# HMC2003_module.net
KiCad netlist of a schematic drawn in Altium Designer
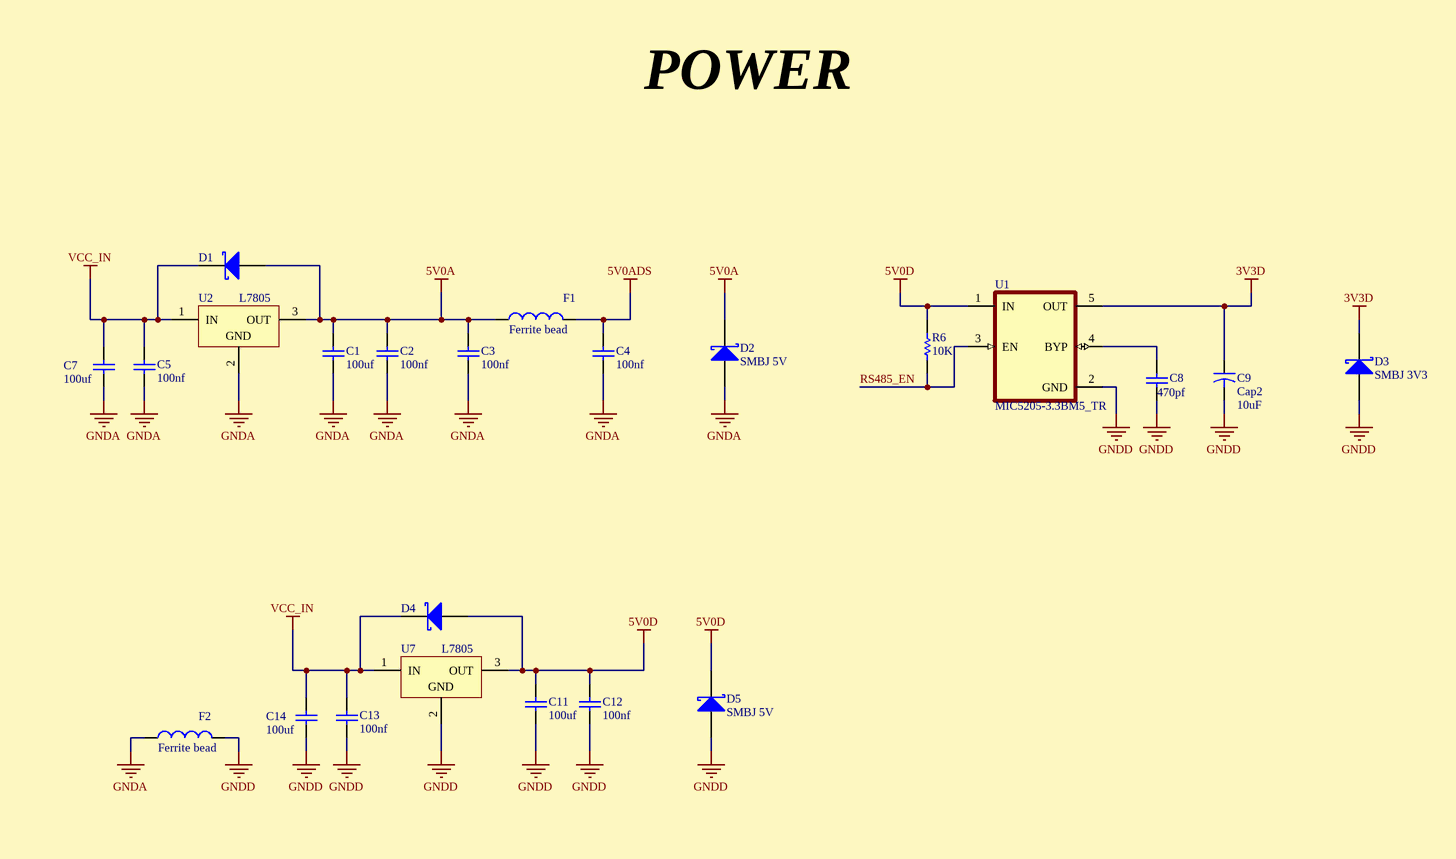
[diagram p0: HMC2003_module.SchDoc, top left]
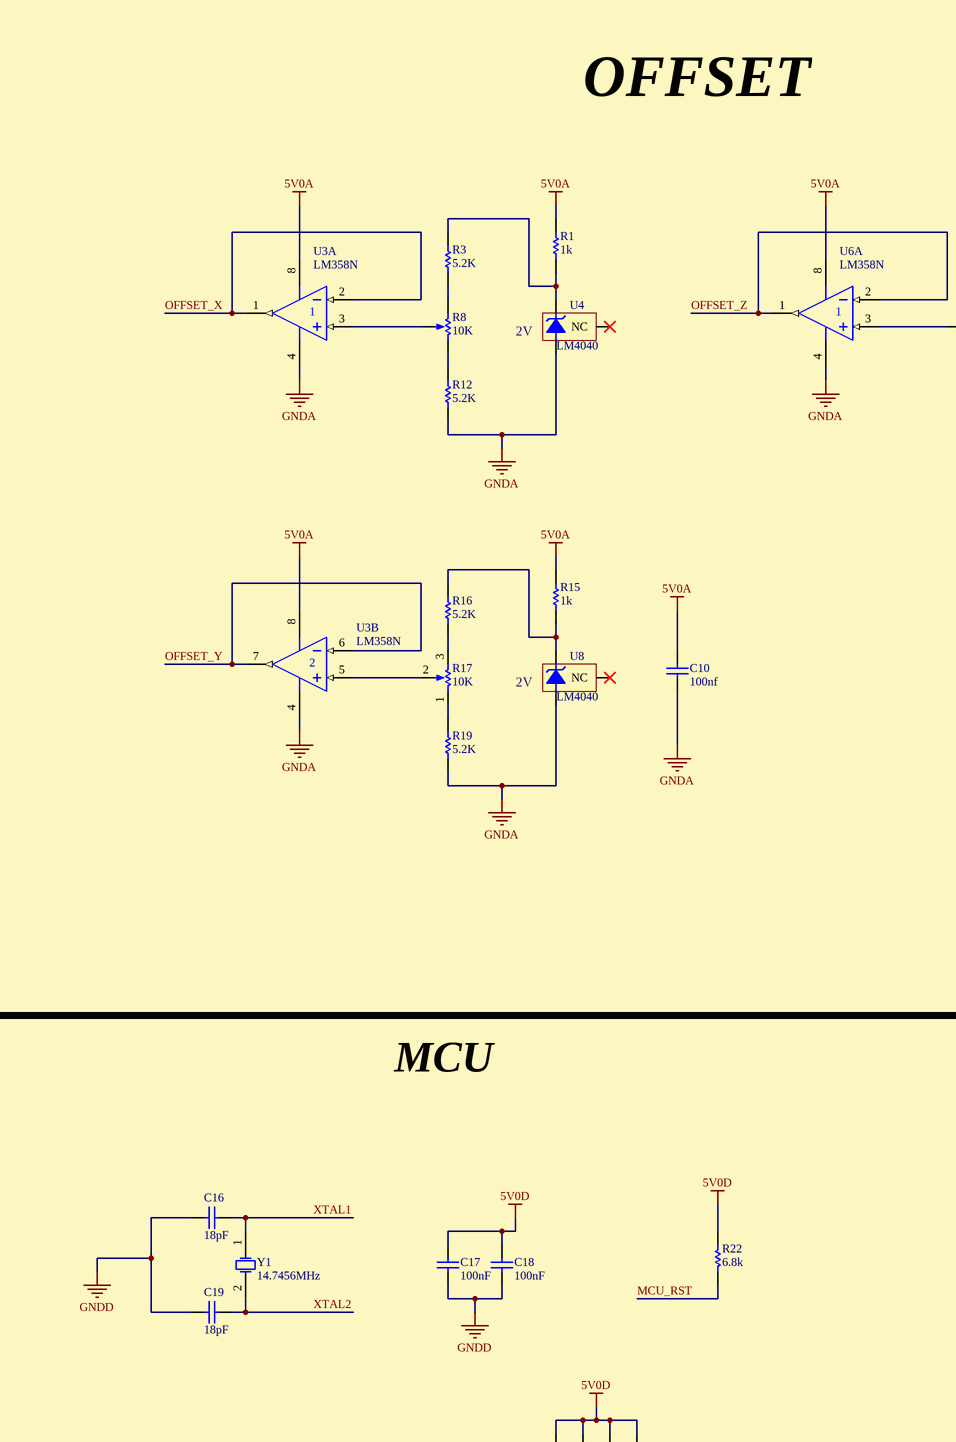
[diagram p1: HMC2003_module.SchDoc, top middle]
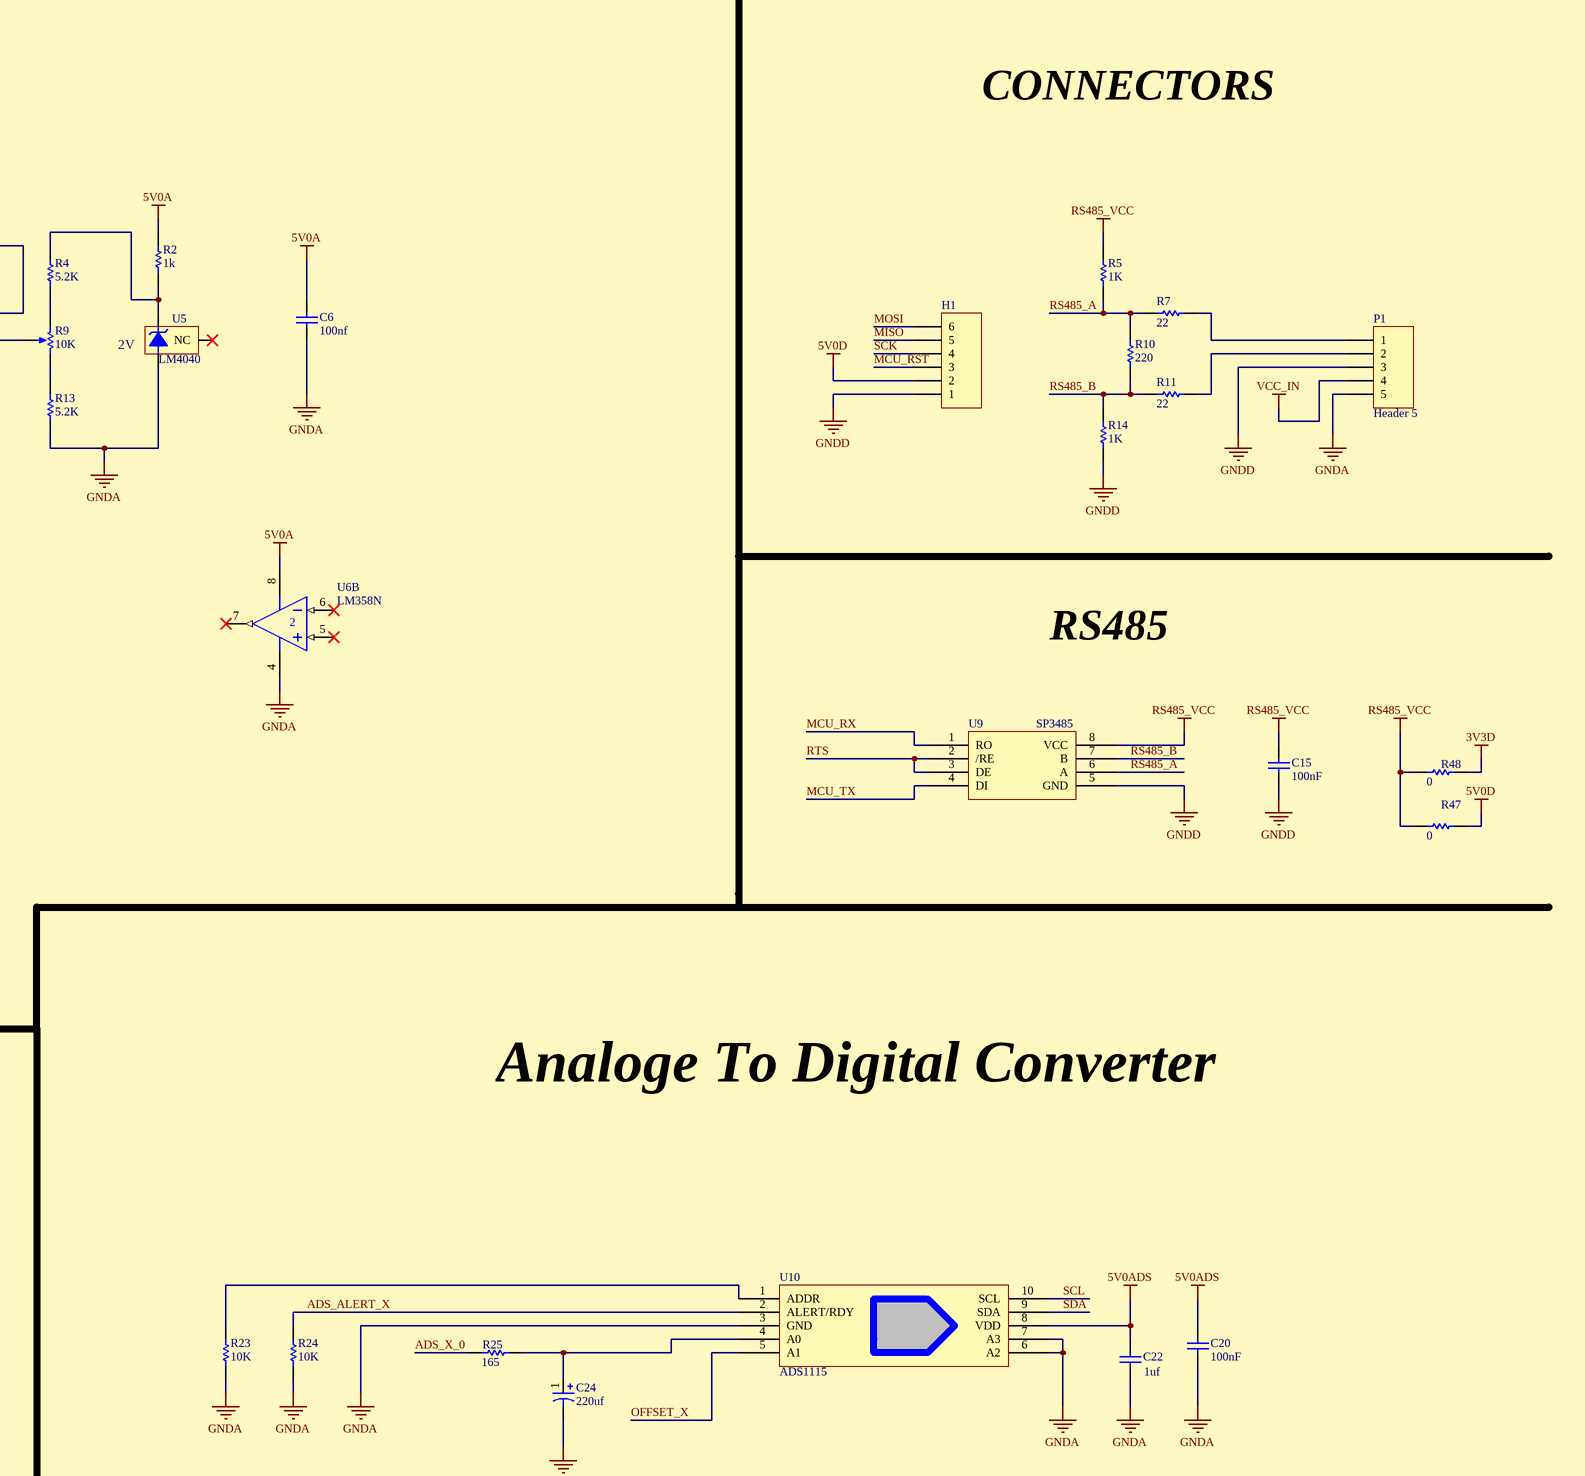
[diagram p2: HMC2003_module.SchDoc, top right]
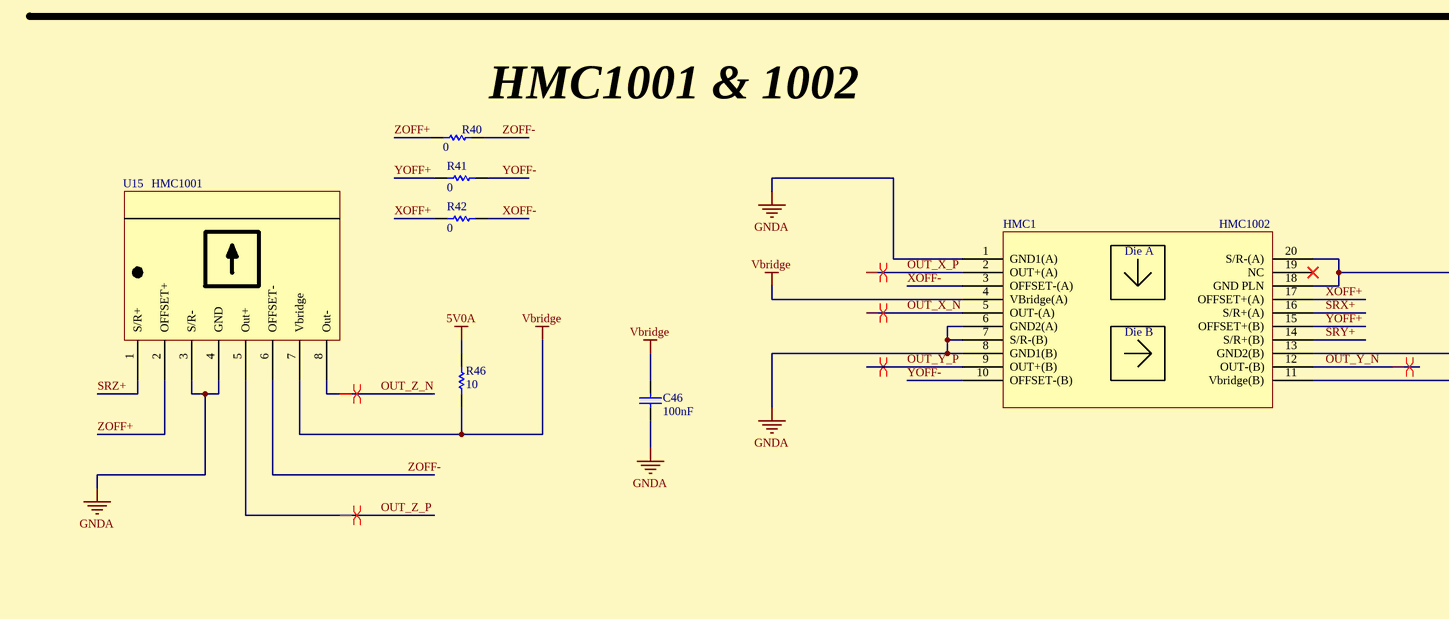
[diagram p3: HMC2003_module.SchDoc, bottom left]
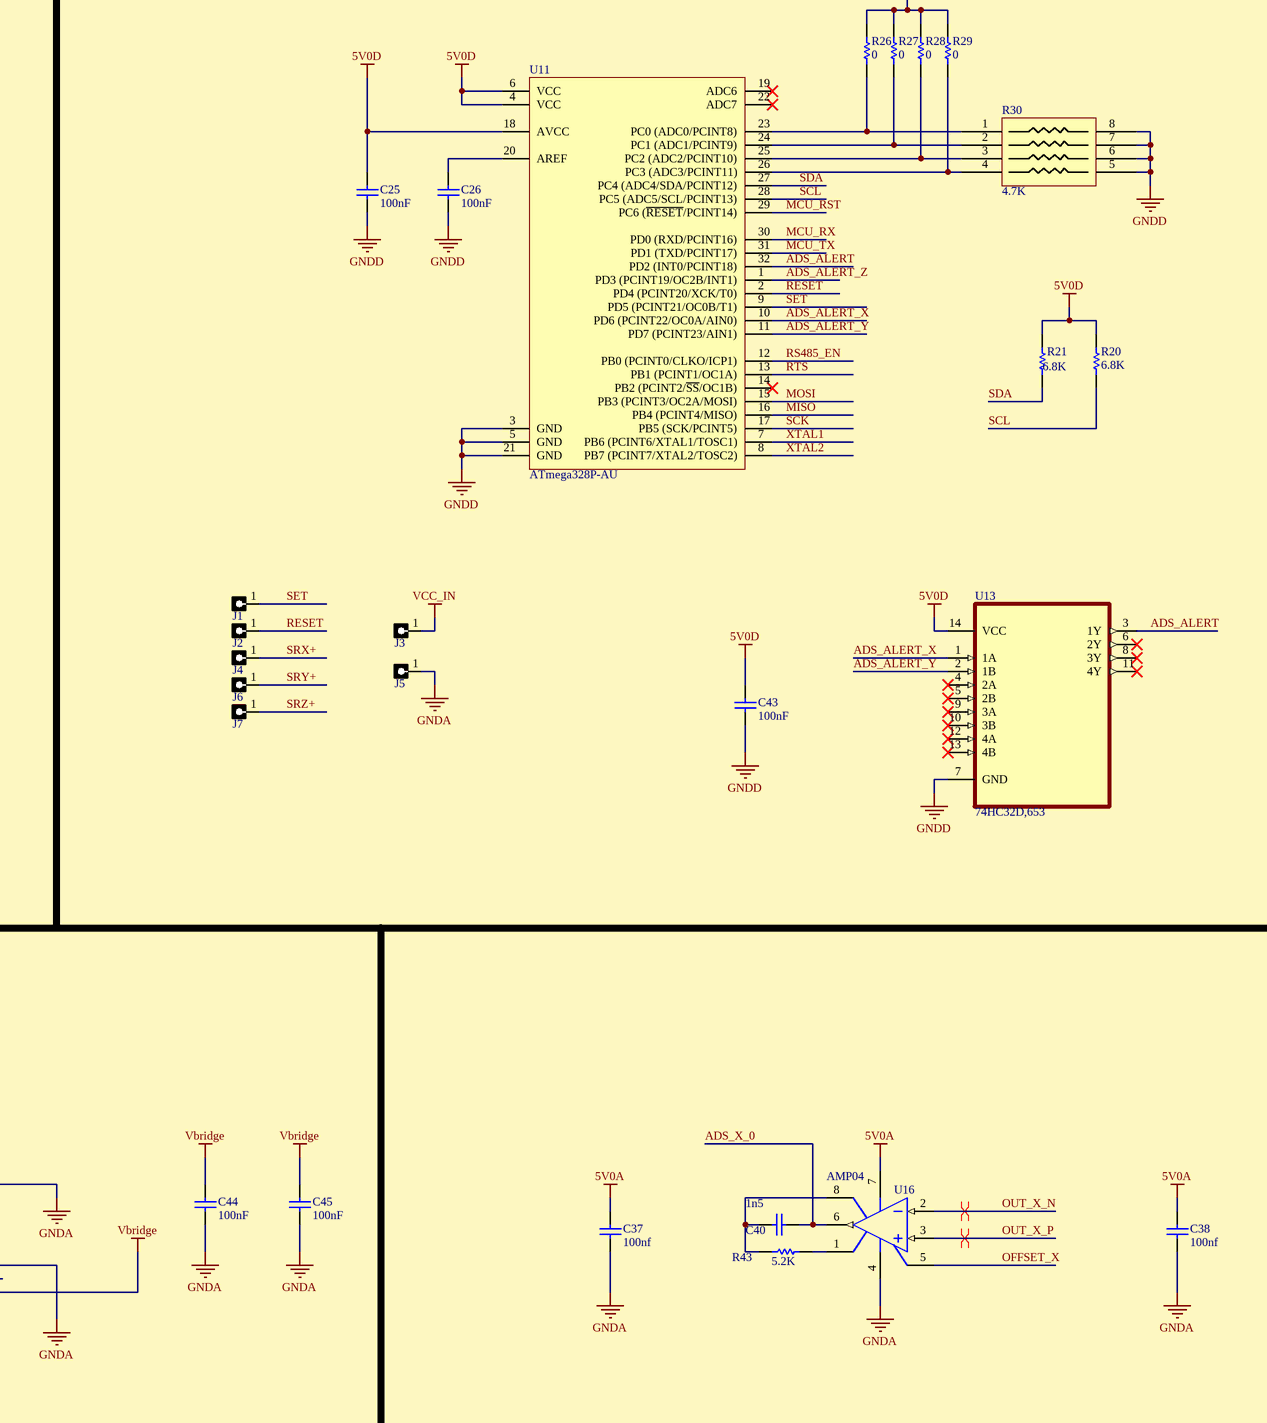
[diagram p4: HMC2003_module.SchDoc, bottom middle]
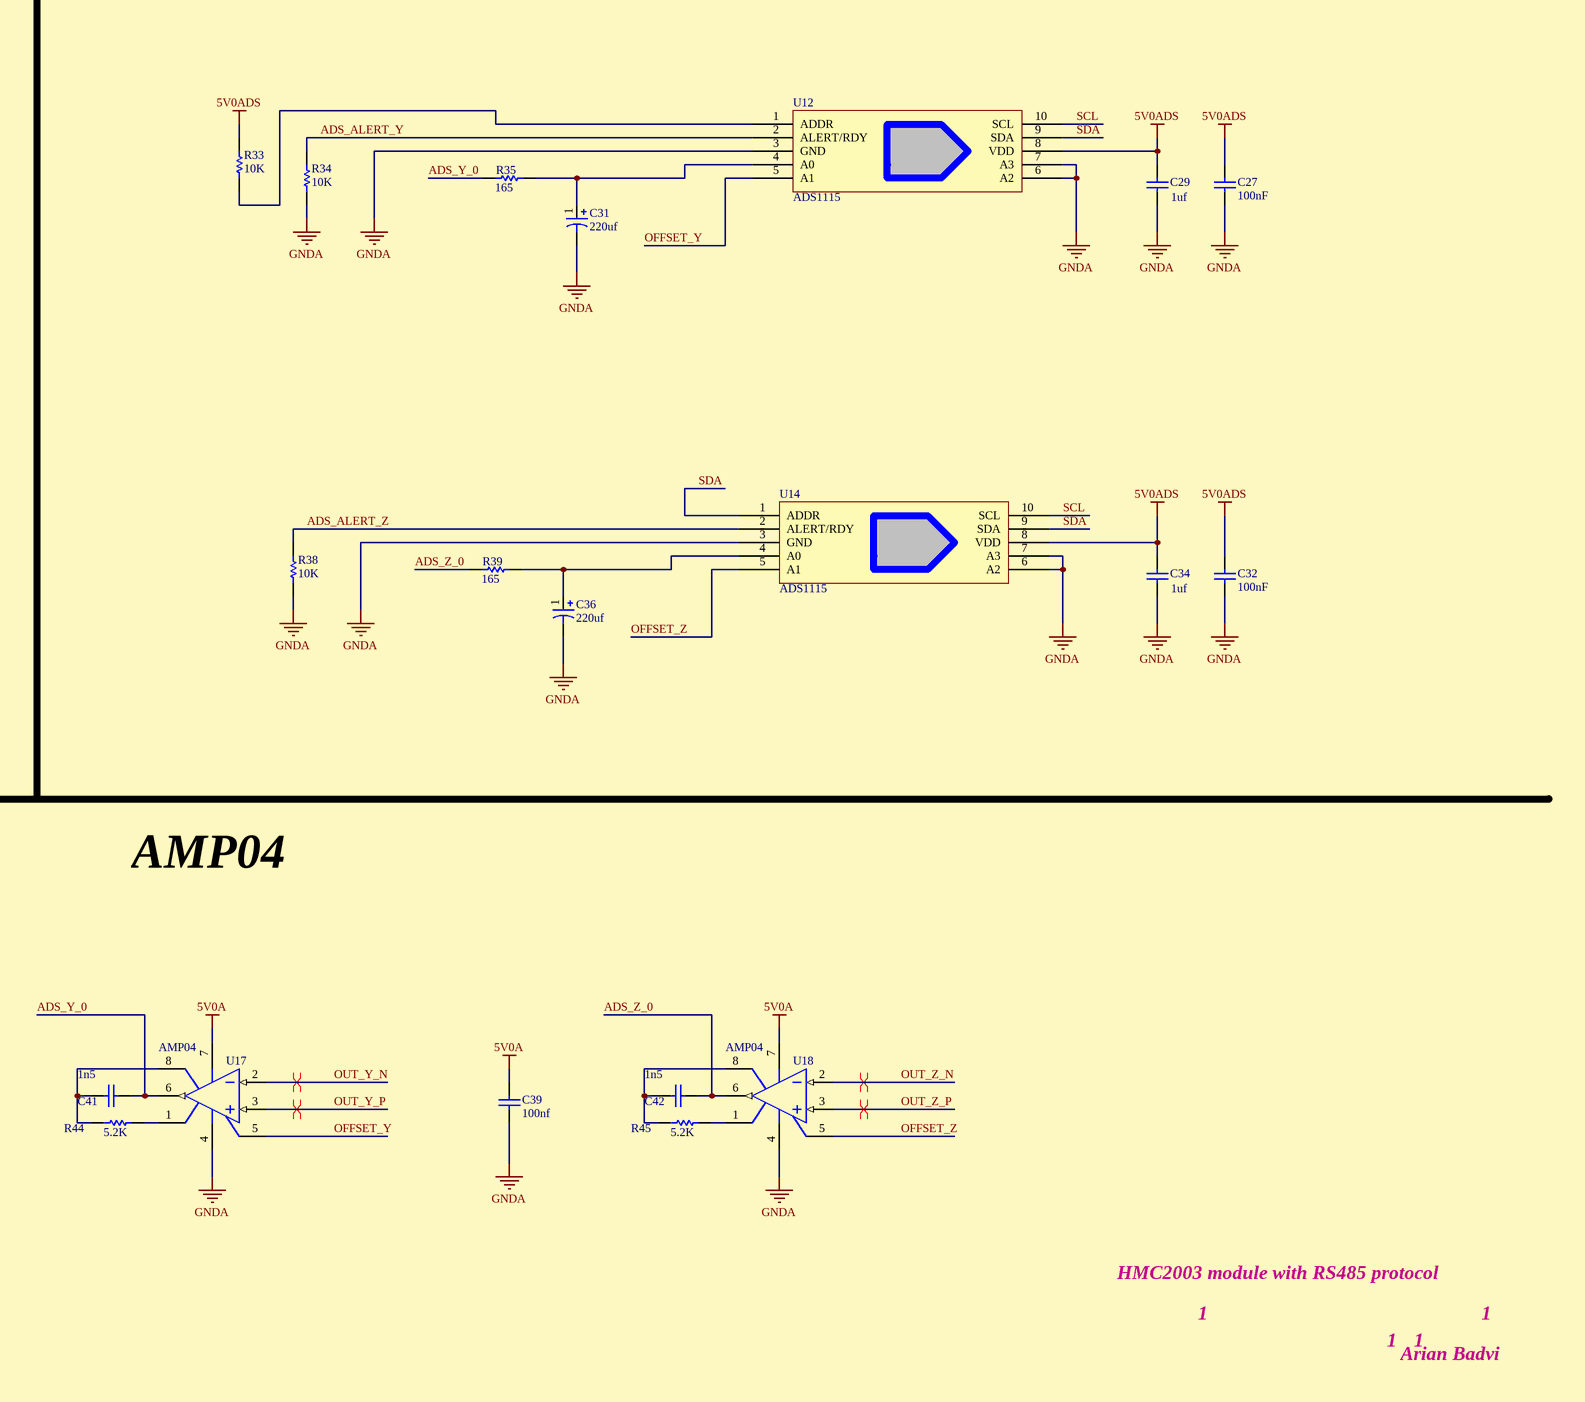
[diagram p5: HMC2003_module.SchDoc, bottom right]

(export (version "E")
  (design (tool "Eeschema 10.0.6"))
  (components
    (comp (ref "C1")
      (value "100uf")
      (footprint "C1206")
      (description "Capacitor, 1206")
      (fields (field (name "PUBLISHER") "Altium Limited"))
      (libsource (lib "Miscellaneous Devices") (part "Cap"))
    )
    (comp (ref "C2")
      (value "100nf")
      (footprint "C0805")
      (description "Capacitor, 1206")
      (fields (field (name "PUBLISHER") "Altium Limited"))
      (libsource (lib "Miscellaneous Devices") (part "Cap"))
    )
    (comp (ref "C3")
      (value "100nf")
      (footprint "C0805")
      (description "Capacitor, 1206")
      (fields (field (name "PUBLISHER") "Altium Limited"))
      (libsource (lib "Miscellaneous Devices") (part "Cap"))
    )
    (comp (ref "C4")
      (value "100nf")
      (footprint "C0805")
      (description "Capacitor, 1206")
      (fields (field (name "PUBLISHER") "Altium Limited"))
      (libsource (lib "Miscellaneous Devices") (part "Cap"))
    )
    (comp (ref "C5")
      (value "100nf")
      (footprint "C0805")
      (description "Capacitor, 1206")
      (fields (field (name "PUBLISHER") "Altium Limited"))
      (libsource (lib "Miscellaneous Devices") (part "Cap"))
    )
    (comp (ref "C6")
      (value "100nf")
      (footprint "C0805")
      (description "Capacitor")
      (fields (field (name "PUBLISHER") "Altium Limited"))
      (libsource (lib "Miscellaneous Devices") (part "Cap"))
    )
    (comp (ref "C7")
      (value "100uf")
      (footprint "C1206")
      (description "Capacitor, 1206")
      (fields (field (name "PUBLISHER") "Altium Limited"))
      (libsource (lib "Miscellaneous Devices") (part "Cap"))
    )
    (comp (ref "C8")
      (value "470pf")
      (footprint "C0805")
      (description "Capacitor, 1206")
      (fields (field (name "PUBLISHER") "Altium Limited"))
      (libsource (lib "Library") (part "Cap"))
    )
    (comp (ref "C9")
      (value "Cap2")
      (footprint "CAP_SMD_A")
      (description "Capacitor, 10uf")
      (fields (field (name "ALTIUM_VALUE") "10uF") (field (name "PUBLISHER") "Altium Limited"))
      (libsource (lib "Miscellaneous Devices") (part "Cap2"))
    )
    (comp (ref "C10")
      (value "100nf")
      (footprint "C0805")
      (description "Capacitor")
      (fields (field (name "PUBLISHER") "Altium Limited"))
      (libsource (lib "Miscellaneous Devices") (part "Cap"))
    )
    (comp (ref "C11")
      (value "100uf")
      (footprint "C1206")
      (description "Capacitor, 1206")
      (fields (field (name "PUBLISHER") "Altium Limited"))
      (libsource (lib "Miscellaneous Devices") (part "Cap"))
    )
    (comp (ref "C12")
      (value "100nf")
      (footprint "C0805")
      (description "Capacitor, 1206")
      (fields (field (name "PUBLISHER") "Altium Limited"))
      (libsource (lib "Miscellaneous Devices") (part "Cap"))
    )
    (comp (ref "C13")
      (value "100nf")
      (footprint "C0805")
      (description "Capacitor, 1206")
      (fields (field (name "PUBLISHER") "Altium Limited"))
      (libsource (lib "Miscellaneous Devices") (part "Cap"))
    )
    (comp (ref "C14")
      (value "100uf")
      (footprint "C1206")
      (description "Capacitor, 1206")
      (fields (field (name "PUBLISHER") "Altium Limited"))
      (libsource (lib "Miscellaneous Devices") (part "Cap"))
    )
    (comp (ref "C15")
      (value "100nF")
      (footprint "C0805")
      (description "Capacitor")
      (fields (field (name "PUBLISHER") "Altium Limited"))
      (libsource (lib "Miscellaneous Devices") (part "Cap"))
    )
    (comp (ref "C16")
      (value "18pF")
      (footprint "C0805")
      (description "Capacitor")
      (fields (field (name "PUBLISHER") "Altium Limited"))
      (libsource (lib "Miscellaneous Devices") (part "Cap"))
    )
    (comp (ref "C17")
      (value "100nF")
      (footprint "C0805")
      (description "Capacitor")
      (fields (field (name "PUBLISHER") "Altium Limited"))
      (libsource (lib "Miscellaneous Devices") (part "Cap"))
    )
    (comp (ref "C18")
      (value "100nF")
      (footprint "C0805")
      (description "Capacitor")
      (fields (field (name "PUBLISHER") "Altium Limited"))
      (libsource (lib "Miscellaneous Devices") (part "Cap"))
    )
    (comp (ref "C19")
      (value "18pF")
      (footprint "C0805")
      (description "Capacitor")
      (fields (field (name "PUBLISHER") "Altium Limited"))
      (libsource (lib "Miscellaneous Devices") (part "Cap"))
    )
    (comp (ref "C20")
      (value "100nF")
      (footprint "C0805")
      (description "Capacitor")
      (fields (field (name "PUBLISHER") "Altium Limited"))
      (libsource (lib "Miscellaneous Devices") (part "Cap"))
    )
    (comp (ref "C22")
      (value "1uf")
      (footprint "C0805")
      (description "Capacitor, 1206")
      (fields (field (name "PUBLISHER") "Altium Limited"))
      (libsource (lib "Library") (part "Cap"))
    )
    (comp (ref "C24")
      (value "220uf")
      (footprint "cap_smd_d")
      (description "TAN CAP D SIZE")
      (fields (field (name "PUBLISHER") "Altium Limited"))
      (libsource (lib "Miscellaneous Devices") (part "Cap Pol1"))
    )
    (comp (ref "C25")
      (value "100nF")
      (footprint "C0805")
      (description "Capacitor")
      (fields (field (name "PUBLISHER") "Altium Limited"))
      (libsource (lib "Miscellaneous Devices") (part "Cap"))
    )
    (comp (ref "C26")
      (value "100nF")
      (footprint "C0805")
      (description "Capacitor")
      (fields (field (name "PUBLISHER") "Altium Limited"))
      (libsource (lib "Miscellaneous Devices") (part "Cap"))
    )
    (comp (ref "C27")
      (value "100nF")
      (footprint "C0805")
      (description "Capacitor")
      (fields (field (name "PUBLISHER") "Altium Limited"))
      (libsource (lib "Miscellaneous Devices") (part "Cap"))
    )
    (comp (ref "C29")
      (value "1uf")
      (footprint "C0805")
      (description "Capacitor, 1206")
      (fields (field (name "PUBLISHER") "Altium Limited"))
      (libsource (lib "Library") (part "Cap"))
    )
    (comp (ref "C31")
      (value "220uf")
      (footprint "cap_smd_d")
      (description "TAN CAP D SIZE")
      (fields (field (name "PUBLISHER") "Altium Limited"))
      (libsource (lib "Miscellaneous Devices") (part "Cap Pol1"))
    )
    (comp (ref "C32")
      (value "100nF")
      (footprint "C0805")
      (description "Capacitor")
      (fields (field (name "PUBLISHER") "Altium Limited"))
      (libsource (lib "Miscellaneous Devices") (part "Cap"))
    )
    (comp (ref "C34")
      (value "1uf")
      (footprint "C0805")
      (description "Capacitor, 1206")
      (fields (field (name "PUBLISHER") "Altium Limited"))
      (libsource (lib "Library") (part "Cap"))
    )
    (comp (ref "C36")
      (value "220uf")
      (footprint "cap_smd_d")
      (description "TAN CAP D SIZE")
      (fields (field (name "PUBLISHER") "Altium Limited"))
      (libsource (lib "Miscellaneous Devices") (part "Cap Pol1"))
    )
    (comp (ref "C37")
      (value "100nf")
      (footprint "C0805")
      (description "Capacitor")
      (fields (field (name "PUBLISHER") "Altium Limited"))
      (libsource (lib "Miscellaneous Devices") (part "Cap"))
    )
    (comp (ref "C38")
      (value "100nf")
      (footprint "C0805")
      (description "Capacitor")
      (fields (field (name "PUBLISHER") "Altium Limited"))
      (libsource (lib "Miscellaneous Devices") (part "Cap"))
    )
    (comp (ref "C39")
      (value "100nf")
      (footprint "C0805")
      (description "Capacitor")
      (fields (field (name "PUBLISHER") "Altium Limited"))
      (libsource (lib "Miscellaneous Devices") (part "Cap"))
    )
    (comp (ref "C40")
      (value "1n5")
      (footprint "C0805")
      (description "Capacitor")
      (fields (field (name "PUBLISHER") "Altium Limited"))
      (libsource (lib "Library") (part "Cap"))
    )
    (comp (ref "C41")
      (value "1n5")
      (footprint "C0805")
      (description "Capacitor")
      (fields (field (name "PUBLISHER") "Altium Limited"))
      (libsource (lib "Library") (part "Cap"))
    )
    (comp (ref "C42")
      (value "1n5")
      (footprint "C0805")
      (description "Capacitor")
      (fields (field (name "PUBLISHER") "Altium Limited"))
      (libsource (lib "Library") (part "Cap"))
    )
    (comp (ref "C43")
      (value "100nF")
      (footprint "C0805")
      (description "Capacitor")
      (fields (field (name "PUBLISHER") "Altium Limited"))
      (libsource (lib "Miscellaneous Devices") (part "Cap"))
    )
    (comp (ref "C44")
      (value "100nF")
      (footprint "C0805")
      (description "Capacitor")
      (fields (field (name "PUBLISHER") "Altium Limited"))
      (libsource (lib "Miscellaneous Devices") (part "Cap"))
    )
    (comp (ref "C45")
      (value "100nF")
      (footprint "C0805")
      (description "Capacitor")
      (fields (field (name "PUBLISHER") "Altium Limited"))
      (libsource (lib "Miscellaneous Devices") (part "Cap"))
    )
    (comp (ref "C46")
      (value "100nF")
      (footprint "C0805")
      (description "Capacitor")
      (fields (field (name "PUBLISHER") "Altium Limited"))
      (libsource (lib "Miscellaneous Devices") (part "Cap"))
    )
    (comp (ref "D1")
      (value "D Schottky")
      (footprint "ZENER")
      (description "Schottky Diode, 1N4148")
      (fields (field (name "PUBLISHER") "Altium Limited"))
      (libsource (lib "Miscellaneous Devices") (part "D Schottky"))
    )
    (comp (ref "D2")
      (value "SMBJ 5V")
      (footprint "TVS")
      (description "Schottky Rectifier")
      (fields (field (name "PUBLISHER") "Altium Limited"))
      (libsource (lib "") (part "Diode 18TQ045_1"))
    )
    (comp (ref "D3")
      (value "SMBJ 3V3")
      (footprint "TVS")
      (description "TVS")
      (fields (field (name "PUBLISHER") "Altium Limited"))
      (libsource (lib "Miscellaneous Devices") (part "Diode 18TQ045"))
    )
    (comp (ref "D4")
      (value "D Schottky")
      (footprint "ZENER")
      (description "Schottky Diode, 1N4148")
      (fields (field (name "PUBLISHER") "Altium Limited"))
      (libsource (lib "Miscellaneous Devices") (part "D Schottky"))
    )
    (comp (ref "D5")
      (value "SMBJ 5V")
      (footprint "TVS")
      (description "Schottky Rectifier")
      (fields (field (name "PUBLISHER") "Altium Limited"))
      (libsource (lib "") (part "Diode 18TQ045_1"))
    )
    (comp (ref "F1")
      (value "Ferrite bead")
      (footprint "0805")
      (description "Ferrite bead, 1206")
      (fields (field (name "PUBLISHER") "Altium Limited"))
      (libsource (lib "Miscellaneous Devices") (part "Inductor"))
    )
    (comp (ref "F2")
      (value "Ferrite bead")
      (footprint "0805")
      (description "Ferrite bead, 1206")
      (fields (field (name "PUBLISHER") "Altium Limited"))
      (libsource (lib "Miscellaneous Devices") (part "Inductor"))
    )
    (comp (ref "H1")
      (value "White SMD Connector 6pin")
      (footprint "PB_6_SMD")
      (fields (field (name "PUBLISHER") "Altium Limited"))
      (libsource (lib "Miscellaneous Connectors") (part "Header 6"))
    )
    (comp (ref "HMC1") (value "HMC1002") (footprint "SO_20_W") (libsource (lib "HMC1002") (part "HMC1002")))
    (comp (ref "J1")
      (value "HDRF1")
      (footprint "HDR_F_1")
      (description "CONN, HEADER, Female, pitch: 2.54mm, 1POS")
      (libsource (lib "A7DDS") (part "HDR_F_1"))
    )
    (comp (ref "J2")
      (value "HDRF1")
      (footprint "HDR_F_1")
      (description "CONN, HEADER, Female, pitch: 2.54mm, 1POS")
      (libsource (lib "A7DDS") (part "HDR_F_1"))
    )
    (comp (ref "J3")
      (value "HDRF1")
      (footprint "HDR_F_1")
      (description "CONN, HEADER, Female, pitch: 2.54mm, 1POS")
      (libsource (lib "A7DDS") (part "HDR_F_1"))
    )
    (comp (ref "J4")
      (value "HDRF1")
      (footprint "HDR_F_1")
      (description "CONN, HEADER, Female, pitch: 2.54mm, 1POS")
      (libsource (lib "A7DDS") (part "HDR_F_1"))
    )
    (comp (ref "J5")
      (value "HDRF1")
      (footprint "HDR_F_1")
      (description "CONN, HEADER, Female, pitch: 2.54mm, 1POS")
      (libsource (lib "A7DDS") (part "HDR_F_1"))
    )
    (comp (ref "J6")
      (value "HDRF1")
      (footprint "HDR_F_1")
      (description "CONN, HEADER, Female, pitch: 2.54mm, 1POS")
      (libsource (lib "A7DDS") (part "HDR_F_1"))
    )
    (comp (ref "J7")
      (value "HDRF1")
      (footprint "HDR_F_1")
      (description "CONN, HEADER, Female, pitch: 2.54mm, 1POS")
      (libsource (lib "A7DDS") (part "HDR_F_1"))
    )
    (comp (ref "P1")
      (value "Header 5")
      (footprint "HDR_M_1x5")
      (description "Header, 5-Pin")
      (fields (field (name "PUBLISHER") "Altium Limited"))
      (libsource (lib "Miscellaneous Connectors") (part "Header 5"))
    )
    (comp (ref "R1")
      (value "1k")
      (footprint "0805")
      (description "Resistor")
      (fields (field (name "PUBLISHER") "Seyed Razi Vesali") (field (name "EMAIL") "razi.vesali@gmail.com"))
      (libsource (lib "resistor1") (part "Resistor"))
    )
    (comp (ref "R2")
      (value "1k")
      (footprint "0805")
      (description "Resistor")
      (fields (field (name "PUBLISHER") "Seyed Razi Vesali") (field (name "EMAIL") "razi.vesali@gmail.com"))
      (libsource (lib "resistor1") (part "Resistor"))
    )
    (comp (ref "R3")
      (value "5.2K")
      (footprint "0805")
      (description "General Resistor")
      (fields (field (name "PUBLISHER") "Altium Limited"))
      (libsource (lib "Library") (part "Resistor"))
    )
    (comp (ref "R4")
      (value "5.2K")
      (footprint "0805")
      (description "General Resistor")
      (fields (field (name "PUBLISHER") "Altium Limited"))
      (libsource (lib "Library") (part "Resistor"))
    )
    (comp (ref "R5")
      (value "1K")
      (footprint "0805")
      (description "Resistor")
      (fields (field (name "PUBLISHER") "Altium Limited"))
      (libsource (lib "Miscellaneous Devices") (part "Res1"))
    )
    (comp (ref "R6")
      (value "10K")
      (footprint "0805")
      (description "General Resistor")
      (fields (field (name "PUBLISHER") "Altium Limited"))
      (libsource (lib "Library") (part "Resistor"))
    )
    (comp (ref "R7")
      (value "22")
      (footprint "0805")
      (description "Resistor")
      (fields (field (name "PUBLISHER") "Altium Limited"))
      (libsource (lib "Miscellaneous Devices") (part "Res1"))
    )
    (comp (ref "R8")
      (value "10K")
      (footprint "POT_3296w")
      (description "Potentiometer")
      (fields (field (name "Comment") "RPot") (field (name "PUBLISHER") "Altium Limited"))
      (libsource (lib "") (part "RPot_1"))
    )
    (comp (ref "R9")
      (value "10K")
      (footprint "POT_3296w")
      (description "Potentiometer")
      (fields (field (name "Comment") "RPot") (field (name "PUBLISHER") "Altium Limited"))
      (libsource (lib "") (part "RPot_1"))
    )
    (comp (ref "R10")
      (value "220")
      (footprint "0805")
      (description "Resistor")
      (fields (field (name "PUBLISHER") "Altium Limited"))
      (libsource (lib "Miscellaneous Devices") (part "Res1"))
    )
    (comp (ref "R11")
      (value "22")
      (footprint "0805")
      (description "Resistor")
      (fields (field (name "PUBLISHER") "Altium Limited"))
      (libsource (lib "Miscellaneous Devices") (part "Res1"))
    )
    (comp (ref "R12")
      (value "5.2K")
      (footprint "0805")
      (description "General Resistor")
      (fields (field (name "PUBLISHER") "Altium Limited"))
      (libsource (lib "Library") (part "Resistor"))
    )
    (comp (ref "R13")
      (value "5.2K")
      (footprint "0805")
      (description "General Resistor")
      (fields (field (name "PUBLISHER") "Altium Limited"))
      (libsource (lib "Library") (part "Resistor"))
    )
    (comp (ref "R14")
      (value "1K")
      (footprint "0805")
      (description "Resistor")
      (fields (field (name "PUBLISHER") "Altium Limited"))
      (libsource (lib "Miscellaneous Devices") (part "Res1"))
    )
    (comp (ref "R15")
      (value "1k")
      (footprint "0805")
      (description "Resistor")
      (fields (field (name "PUBLISHER") "Seyed Razi Vesali") (field (name "EMAIL") "razi.vesali@gmail.com"))
      (libsource (lib "resistor1") (part "Resistor"))
    )
    (comp (ref "R16")
      (value "5.2K")
      (footprint "0805")
      (description "General Resistor")
      (fields (field (name "PUBLISHER") "Altium Limited"))
      (libsource (lib "Library") (part "Resistor"))
    )
    (comp (ref "R17")
      (value "10K")
      (footprint "POT_3296w")
      (description "Potentiometer")
      (fields (field (name "Comment") "RPot") (field (name "PUBLISHER") "Altium Limited"))
      (libsource (lib "Miscellaneous Devices") (part "RPot"))
    )
    (comp (ref "R19")
      (value "5.2K")
      (footprint "0805")
      (description "General Resistor")
      (fields (field (name "PUBLISHER") "Altium Limited"))
      (libsource (lib "Library") (part "Resistor"))
    )
    (comp (ref "R20")
      (value "6.8K")
      (footprint "0805")
      (description "General Resistor")
      (fields (field (name "PUBLISHER") "Altium Limited"))
      (libsource (lib "Library") (part "Resistor"))
    )
    (comp (ref "R21")
      (value "6.8K")
      (footprint "0805")
      (description "General Resistor")
      (fields (field (name "PUBLISHER") "Altium Limited"))
      (libsource (lib "Library") (part "Resistor"))
    )
    (comp (ref "R22")
      (value "6.8k")
      (footprint "0805")
      (description "Resistor, 6.8k")
      (fields (field (name "PUBLISHER") "Altium Limited"))
      (libsource (lib "Miscellaneous Devices") (part "Res1"))
    )
    (comp (ref "R23")
      (value "10K")
      (footprint "0805")
      (description "General Resistor")
      (fields (field (name "PUBLISHER") "Altium Limited"))
      (libsource (lib "Library") (part "Resistor"))
    )
    (comp (ref "R24")
      (value "10K")
      (footprint "0805")
      (description "General Resistor")
      (fields (field (name "PUBLISHER") "Altium Limited"))
      (libsource (lib "Library") (part "Resistor"))
    )
    (comp (ref "R25")
      (value "165")
      (footprint "0805")
      (description "General Resistor")
      (fields (field (name "PUBLISHER") "Altium Limited"))
      (libsource (lib "Library") (part "Resistor"))
    )
    (comp (ref "R26")
      (value "0")
      (footprint "0603")
      (description "Resistor, 6.8k")
      (fields (field (name "PUBLISHER") "Altium Limited"))
      (libsource (lib "Miscellaneous Devices") (part "Res1"))
    )
    (comp (ref "R27")
      (value "0")
      (footprint "0603")
      (description "Resistor, 6.8k")
      (fields (field (name "PUBLISHER") "Altium Limited"))
      (libsource (lib "Miscellaneous Devices") (part "Res1"))
    )
    (comp (ref "R28")
      (value "0")
      (footprint "0603")
      (description "Resistor, 6.8k")
      (fields (field (name "PUBLISHER") "Altium Limited"))
      (libsource (lib "Miscellaneous Devices") (part "Res1"))
    )
    (comp (ref "R29")
      (value "0")
      (footprint "0603")
      (description "Resistor, 6.8k")
      (fields (field (name "PUBLISHER") "Altium Limited"))
      (libsource (lib "Miscellaneous Devices") (part "Res1"))
    )
    (comp (ref "R30")
      (value "4.7K")
      (footprint "RP0603X4")
      (libsource (lib "RES_ARRAY_4") (part "RES_ARRAY_4"))
    )
    (comp (ref "R33")
      (value "10K")
      (footprint "0805")
      (description "General Resistor")
      (fields (field (name "PUBLISHER") "Altium Limited"))
      (libsource (lib "Library") (part "Resistor"))
    )
    (comp (ref "R34")
      (value "10K")
      (footprint "0805")
      (description "General Resistor")
      (fields (field (name "PUBLISHER") "Altium Limited"))
      (libsource (lib "Library") (part "Resistor"))
    )
    (comp (ref "R35")
      (value "165")
      (footprint "0805")
      (description "General Resistor")
      (fields (field (name "PUBLISHER") "Altium Limited"))
      (libsource (lib "Library") (part "Resistor"))
    )
    (comp (ref "R38")
      (value "10K")
      (footprint "0805")
      (description "General Resistor")
      (fields (field (name "PUBLISHER") "Altium Limited"))
      (libsource (lib "Library") (part "Resistor"))
    )
    (comp (ref "R39")
      (value "165")
      (footprint "0805")
      (description "General Resistor")
      (fields (field (name "PUBLISHER") "Altium Limited"))
      (libsource (lib "Library") (part "Resistor"))
    )
    (comp (ref "R40")
      (value "0")
      (footprint "0603")
      (description "Resistor")
      (fields (field (name "PUBLISHER") "Seyed Razi Vesali") (field (name "EMAIL") "razi.vesali@gmail.com"))
      (libsource (lib "resistor1") (part "Resistor"))
    )
    (comp (ref "R41")
      (value "0")
      (footprint "0603")
      (description "Resistor")
      (fields (field (name "PUBLISHER") "Seyed Razi Vesali") (field (name "EMAIL") "razi.vesali@gmail.com"))
      (libsource (lib "resistor1") (part "Resistor"))
    )
    (comp (ref "R42")
      (value "0")
      (footprint "0603")
      (description "Resistor")
      (fields (field (name "PUBLISHER") "Seyed Razi Vesali") (field (name "EMAIL") "razi.vesali@gmail.com"))
      (libsource (lib "resistor1") (part "Resistor"))
    )
    (comp (ref "R43")
      (value "5.2K")
      (footprint "0805")
      (description "General Resistor")
      (fields (field (name "PUBLISHER") "Altium Limited"))
      (libsource (lib "Library") (part "Resistor"))
    )
    (comp (ref "R44")
      (value "5.2K")
      (footprint "0805")
      (description "General Resistor")
      (fields (field (name "PUBLISHER") "Altium Limited"))
      (libsource (lib "Library") (part "Resistor"))
    )
    (comp (ref "R45")
      (value "5.2K")
      (footprint "0805")
      (description "General Resistor")
      (fields (field (name "PUBLISHER") "Altium Limited"))
      (libsource (lib "Library") (part "Resistor"))
    )
    (comp (ref "R46")
      (value "10")
      (footprint "0805")
      (description "Resistor")
      (fields (field (name "PUBLISHER") "Seyed Razi Vesali") (field (name "EMAIL") "razi.vesali@gmail.com"))
      (libsource (lib "resistor1") (part "Resistor"))
    )
    (comp (ref "R47")
      (value "0")
      (footprint "0603")
      (description "Resistor")
      (fields (field (name "PUBLISHER") "Seyed Razi Vesali") (field (name "EMAIL") "razi.vesali@gmail.com"))
      (libsource (lib "resistor1") (part "Resistor"))
    )
    (comp (ref "R48")
      (value "0")
      (footprint "0603")
      (description "Resistor")
      (fields (field (name "PUBLISHER") "Seyed Razi Vesali") (field (name "EMAIL") "razi.vesali@gmail.com"))
      (libsource (lib "resistor1") (part "Resistor"))
    )
    (comp (ref "U1")
      (value "MIC5205-3.3BM5_TR")
      (footprint "SOT23_5")
      (description "Linear Voltage Regulator IC 1 Output 150mA SOT-23-5")
      (fields (field (name "MP") "MIC5205-3.3BM5 TR") (field (name "MF") "Micrel"))
      (libsource (lib "Main_board") (part "MIC5205-3.3BM5_TR"))
    )
    (comp (ref "U2")
      (value "L7805")
      (footprint "DPAK")
      (description "Positive Voltage Regulator")
      (fields (field (name "PUBLISHER") "Altium Limited"))
      (libsource (lib "ST Power Mgt Voltage Regulator") (part "L7805CD2T"))
    )
    (comp (ref "U3")
      (value "LM358N")
      (footprint "sop8")
      (description "Dual Low-Power Operational Amplifier")
      (fields (field (name "PUBLISHER") "Altium Limited"))
      (libsource (lib "Motorola Amplifier Operational Amplifier") (part "LM358N"))
    )
    (comp (ref "U4")
      (value "LM4040")
      (footprint "sot-23")
      (description "Precision Micropower Shunt Voltage Reference, 3-pin SOT-23")
      (fields
        (field (name "PARTNUMBER") "LM4040DIM3-10.0")
        (field (name "MANUFACTURER") "National Semiconductor")
        (field (name "PUBLISHER") "Altium Limited")
      )
      (libsource (lib "final_sensor_sch_lib") (part "LM4040"))
    )
    (comp (ref "U5")
      (value "LM4040")
      (footprint "sot-23")
      (description "Precision Micropower Shunt Voltage Reference, 3-pin SOT-23")
      (fields
        (field (name "PARTNUMBER") "LM4040DIM3-10.0")
        (field (name "MANUFACTURER") "National Semiconductor")
        (field (name "PUBLISHER") "Altium Limited")
      )
      (libsource (lib "final_sensor_sch_lib") (part "LM4040"))
    )
    (comp (ref "U6")
      (value "LM358N")
      (footprint "sop8")
      (description "Dual Low-Power Operational Amplifier")
      (fields (field (name "PUBLISHER") "Altium Limited"))
      (libsource (lib "Motorola Amplifier Operational Amplifier") (part "LM358N"))
    )
    (comp (ref "U7")
      (value "L7805")
      (footprint "DPAK")
      (description "Positive Voltage Regulator")
      (fields (field (name "PUBLISHER") "Altium Limited"))
      (libsource (lib "ST Power Mgt Voltage Regulator") (part "L7805CD2T"))
    )
    (comp (ref "U8")
      (value "LM4040")
      (footprint "sot-23")
      (description "Precision Micropower Shunt Voltage Reference, 3-pin SOT-23")
      (fields
        (field (name "PARTNUMBER") "LM4040DIM3-10.0")
        (field (name "MANUFACTURER") "National Semiconductor")
        (field (name "PUBLISHER") "Altium Limited")
      )
      (libsource (lib "final_sensor_sch_lib") (part "LM4040"))
    )
    (comp (ref "U9") (value "SP3485") (footprint "SOP8") (libsource (lib "Schlib_RS485") (part "rs485")))
    (comp (ref "U10") (value "ADS1115") (footprint "TSSOP10_N") (libsource (lib "Library") (part "ADS1115")))
    (comp (ref "U11")
      (value "ATmega328P-AU")
      (footprint "32A_L")
      (fields (field (name "PUBLISHER") "Altium Limited"))
      (libsource (lib "Library") (part "ATmega328P-AU"))
    )
    (comp (ref "U12") (value "ADS1115") (footprint "TSSOP10_N") (libsource (lib "Library") (part "ADS1115")))
    (comp (ref "U13")
      (value "74HC32D,653")
      (footprint "SOG65_14")
      (description "OR Gate IC 4 Channel 14-SO")
      (fields (field (name "MF") "Nexperia USA"))
      (libsource (lib "74HC32D_653") (part "74HC32D,653"))
    )
    (comp (ref "U14") (value "ADS1115") (footprint "TSSOP10_N") (libsource (lib "Library") (part "ADS1115")))
    (comp (ref "U15") (value "HMC1001") (footprint "HMC1001_V") (libsource (lib "Library") (part "HMC1001")))
    (comp (ref "U16")
      (value "AMP04")
      (footprint "sop8")
      (fields (field (name "PUBLISHER") "Altium Limited"))
      (libsource (lib "Miscellaneous Devices") (part "Op Amp"))
    )
    (comp (ref "U17")
      (value "AMP04")
      (footprint "sop8")
      (fields (field (name "PUBLISHER") "Altium Limited"))
      (libsource (lib "Miscellaneous Devices") (part "Op Amp"))
    )
    (comp (ref "U18")
      (value "AMP04")
      (footprint "sop8")
      (fields (field (name "PUBLISHER") "Altium Limited"))
      (libsource (lib "Miscellaneous Devices") (part "Op Amp"))
    )
    (comp (ref "Y1")
      (value "14.7456MHz")
      (footprint "XTAL_SMD")
      (description "Crystal Oscillator, 14.7456KHz")
      (fields (field (name "PUBLISHER") "Altium Limited"))
      (libsource (lib "Miscellaneous Devices") (part "XTAL"))
    )
  )
  (nets
    (net (code "1") (name "/ADS_ALERT") (class "Default")
      (node (ref "U11") (pin "32") (pinfunction "PD2_(INT0/PCINT18)_32") (pintype "passive"))
      (node (ref "U13") (pin "3") (pinfunction "1Y_3") (pintype "output"))
    )
    (net (code "2") (name "/ADS_ALERT_X") (class "Default")
      (node (ref "R24") (pin "2") (pinfunction "2_2") (pintype "passive"))
      (node (ref "U10") (pin "2") (pinfunction "ALERT/RDY_2") (pintype "passive"))
      (node (ref "U11") (pin "10") (pinfunction "PD6_(PCINT22/OC0A/AIN0)_10") (pintype "passive"))
      (node (ref "U13") (pin "1") (pinfunction "1A_1") (pintype "input"))
    )
    (net (code "3") (name "/ADS_ALERT_Y") (class "Default")
      (node (ref "R34") (pin "2") (pinfunction "2_2") (pintype "passive"))
      (node (ref "U11") (pin "11") (pinfunction "PD7_(PCINT23/AIN1)_11") (pintype "passive"))
      (node (ref "U12") (pin "2") (pinfunction "ALERT/RDY_2") (pintype "passive"))
      (node (ref "U13") (pin "2") (pinfunction "1B_2") (pintype "input"))
    )
    (net (code "4") (name "/ADS_ALERT_Z") (class "Default")
      (node (ref "R38") (pin "2") (pinfunction "2_2") (pintype "passive"))
      (node (ref "U11") (pin "1") (pinfunction "PD3_(PCINT19/OC2B/INT1)_1") (pintype "passive"))
      (node (ref "U14") (pin "2") (pinfunction "ALERT/RDY_2") (pintype "passive"))
    )
    (net (code "5") (name "/ADS_X_0") (class "Default")
      (node (ref "C40") (pin "1") (pinfunction "1_1") (pintype "passive"))
      (node (ref "R25") (pin "1") (pinfunction "1_1") (pintype "passive"))
      (node (ref "U16") (pin "6") (pinfunction "OUT_6") (pintype "output"))
    )
    (net (code "6") (name "/ADS_Y_0") (class "Default")
      (node (ref "C41") (pin "1") (pinfunction "1_1") (pintype "passive"))
      (node (ref "R35") (pin "1") (pinfunction "1_1") (pintype "passive"))
      (node (ref "U17") (pin "6") (pinfunction "OUT_6") (pintype "output"))
    )
    (net (code "7") (name "/ADS_Z_0") (class "Default")
      (node (ref "C42") (pin "1") (pinfunction "1_1") (pintype "passive"))
      (node (ref "R39") (pin "1") (pinfunction "1_1") (pintype "passive"))
      (node (ref "U18") (pin "6") (pinfunction "OUT_6") (pintype "output"))
    )
    (net (code "8") (name "/MCU_RST") (class "Default")
      (node (ref "H1") (pin "3") (pinfunction "3_3") (pintype "passive"))
      (node (ref "R22") (pin "2") (pinfunction "2_2") (pintype "passive"))
      (node (ref "U11") (pin "29") (pinfunction "PC6_(~{RESET}/PCINT14)_29") (pintype "passive"))
    )
    (net (code "9") (name "/MCU_RX") (class "Default")
      (node (ref "U11") (pin "30") (pinfunction "PD0_(RXD/PCINT16)_30") (pintype "passive"))
      (node (ref "U9") (pin "1") (pinfunction "RO_1") (pintype "passive"))
    )
    (net (code "10") (name "/MCU_TX") (class "Default")
      (node (ref "U11") (pin "31") (pinfunction "PD1_(TXD/PCINT17)_31") (pintype "passive"))
      (node (ref "U9") (pin "4") (pinfunction "DI_4") (pintype "passive"))
    )
    (net (code "11") (name "/MISO") (class "Default")
      (node (ref "H1") (pin "5") (pinfunction "5_5") (pintype "passive"))
      (node (ref "U11") (pin "16") (pinfunction "PB4_(PCINT4/MISO)_16") (pintype "passive"))
    )
    (net (code "12") (name "/MOSI") (class "Default")
      (node (ref "H1") (pin "6") (pinfunction "6_6") (pintype "passive"))
      (node (ref "U11") (pin "15") (pinfunction "PB3_(PCINT3/OC2A/MOSI)_15") (pintype "passive"))
    )
    (net (code "13") (name "/OFFSET_X") (class "Default")
      (node (ref "U10") (pin "5") (pinfunction "A1_5") (pintype "passive"))
      (node (ref "U16") (pin "5") (pinfunction "OS_NUL_5") (pintype "passive"))
      (node (ref "U3") (pin "1") (pinfunction "OUT_1") (pintype "output"))
      (node (ref "U3") (pin "2") (pinfunction "IN-_2") (pintype "input"))
    )
    (net (code "14") (name "/OFFSET_Y") (class "Default")
      (node (ref "U12") (pin "5") (pinfunction "A1_5") (pintype "passive"))
      (node (ref "U17") (pin "5") (pinfunction "OS_NUL_5") (pintype "passive"))
      (node (ref "U3") (pin "6") (pinfunction "IN-_6") (pintype "input"))
      (node (ref "U3") (pin "7") (pinfunction "OUT_7") (pintype "output"))
    )
    (net (code "15") (name "/OFFSET_Z") (class "Default")
      (node (ref "U14") (pin "5") (pinfunction "A1_5") (pintype "passive"))
      (node (ref "U18") (pin "5") (pinfunction "OS_NUL_5") (pintype "passive"))
      (node (ref "U6") (pin "1") (pinfunction "OUT_1") (pintype "output"))
      (node (ref "U6") (pin "2") (pinfunction "IN-_2") (pintype "input"))
    )
    (net (code "16") (name "/OUT_X_N") (class "Default")
      (node (ref "HMC1") (pin "5") (pinfunction "OUT-(A)_5") (pintype "passive"))
      (node (ref "U16") (pin "2") (pinfunction "IN-_2") (pintype "input"))
    )
    (net (code "17") (name "/OUT_X_P") (class "Default")
      (node (ref "HMC1") (pin "2") (pinfunction "OUT+(A)_2") (pintype "passive"))
      (node (ref "U16") (pin "3") (pinfunction "IN+_3") (pintype "input"))
    )
    (net (code "18") (name "/OUT_Y_N") (class "Default")
      (node (ref "HMC1") (pin "12") (pinfunction "OUT-(B)_12") (pintype "passive"))
      (node (ref "U17") (pin "2") (pinfunction "IN-_2") (pintype "input"))
    )
    (net (code "19") (name "/OUT_Y_P") (class "Default")
      (node (ref "HMC1") (pin "9") (pinfunction "OUT+(B)_9") (pintype "passive"))
      (node (ref "U17") (pin "3") (pinfunction "IN+_3") (pintype "input"))
    )
    (net (code "20") (name "/OUT_Z_N") (class "Default")
      (node (ref "U15") (pin "8") (pinfunction "Out-_8") (pintype "passive"))
      (node (ref "U18") (pin "2") (pinfunction "IN-_2") (pintype "input"))
    )
    (net (code "21") (name "/OUT_Z_P") (class "Default")
      (node (ref "U15") (pin "5") (pinfunction "Out+_5") (pintype "passive"))
      (node (ref "U18") (pin "3") (pinfunction "IN+_3") (pintype "input"))
    )
    (net (code "22") (name "/RESET") (class "Default")
      (node (ref "J2") (pin "1") (pinfunction "1_1") (pintype "passive"))
      (node (ref "U11") (pin "2") (pinfunction "PD4_(PCINT20/XCK/T0)_2") (pintype "passive"))
    )
    (net (code "23") (name "/RS485_A") (class "Default")
      (node (ref "R10") (pin "1") (pinfunction "1_1") (pintype "passive"))
      (node (ref "R5") (pin "1") (pinfunction "1_1") (pintype "passive"))
      (node (ref "R7") (pin "1") (pinfunction "1_1") (pintype "passive"))
      (node (ref "U9") (pin "6") (pinfunction "A_6") (pintype "passive"))
    )
    (net (code "24") (name "/RS485_B") (class "Default")
      (node (ref "R10") (pin "2") (pinfunction "2_2") (pintype "passive"))
      (node (ref "R11") (pin "1") (pinfunction "1_1") (pintype "passive"))
      (node (ref "R14") (pin "2") (pinfunction "2_2") (pintype "passive"))
      (node (ref "U9") (pin "7") (pinfunction "B_7") (pintype "passive"))
    )
    (net (code "25") (name "/RS485_EN") (class "Default")
      (node (ref "R6") (pin "2") (pinfunction "2_2") (pintype "passive"))
      (node (ref "U1") (pin "3") (pinfunction "EN_3") (pintype "input"))
      (node (ref "U11") (pin "12") (pinfunction "PB0_(PCINT0/CLKO/ICP1)_12") (pintype "passive"))
    )
    (net (code "26") (name "/RTS") (class "Default")
      (node (ref "U11") (pin "13") (pinfunction "PB1_(PCINT1/OC1A)_13") (pintype "passive"))
      (node (ref "U9") (pin "2") (pinfunction "/RE_2") (pintype "passive"))
      (node (ref "U9") (pin "3") (pinfunction "DE_3") (pintype "passive"))
    )
    (net (code "27") (name "/SCK") (class "Default")
      (node (ref "H1") (pin "4") (pinfunction "4_4") (pintype "passive"))
      (node (ref "U11") (pin "17") (pinfunction "PB5_(SCK/PCINT5)_17") (pintype "passive"))
    )
    (net (code "28") (name "/SCL") (class "Default")
      (node (ref "R20") (pin "2") (pinfunction "2_2") (pintype "passive"))
      (node (ref "U10") (pin "10") (pinfunction "SCL_10") (pintype "passive"))
      (node (ref "U11") (pin "28") (pinfunction "PC5_(ADC5/SCL/PCINT13)_28") (pintype "passive"))
      (node (ref "U12") (pin "10") (pinfunction "SCL_10") (pintype "passive"))
      (node (ref "U14") (pin "10") (pinfunction "SCL_10") (pintype "passive"))
    )
    (net (code "29") (name "/SDA") (class "Default")
      (node (ref "R21") (pin "2") (pinfunction "2_2") (pintype "passive"))
      (node (ref "U10") (pin "9") (pinfunction "SDA_9") (pintype "passive"))
      (node (ref "U11") (pin "27") (pinfunction "PC4_(ADC4/SDA/PCINT12)_27") (pintype "passive"))
      (node (ref "U12") (pin "9") (pinfunction "SDA_9") (pintype "passive"))
      (node (ref "U14") (pin "1") (pinfunction "ADDR_1") (pintype "passive"))
      (node (ref "U14") (pin "9") (pinfunction "SDA_9") (pintype "passive"))
    )
    (net (code "30") (name "/SET") (class "Default")
      (node (ref "J1") (pin "1") (pinfunction "1_1") (pintype "passive"))
      (node (ref "U11") (pin "9") (pinfunction "PD5_(PCINT21/OC0B/T1)_9") (pintype "passive"))
    )
    (net (code "31") (name "/SRX+") (class "Default")
      (node (ref "HMC1") (pin "16") (pinfunction "S/R+(A)_16") (pintype "passive"))
      (node (ref "J4") (pin "1") (pinfunction "1_1") (pintype "passive"))
    )
    (net (code "32") (name "/SRY+") (class "Default")
      (node (ref "HMC1") (pin "14") (pinfunction "S/R+(B)_14") (pintype "passive"))
      (node (ref "J6") (pin "1") (pinfunction "1_1") (pintype "passive"))
    )
    (net (code "33") (name "/SRZ+") (class "Default")
      (node (ref "J7") (pin "1") (pinfunction "1_1") (pintype "passive"))
      (node (ref "U15") (pin "1") (pinfunction "S/R+_1") (pintype "passive"))
    )
    (net (code "34") (name "/XOFF+") (class "Default")
      (node (ref "HMC1") (pin "17") (pinfunction "OFFSET+(A)_17") (pintype "passive"))
      (node (ref "R42") (pin "2") (pinfunction "2_2") (pintype "passive"))
    )
    (net (code "35") (name "/XOFF-") (class "Default")
      (node (ref "HMC1") (pin "3") (pinfunction "OFFSET-(A)_3") (pintype "passive"))
      (node (ref "R42") (pin "1") (pinfunction "1_1") (pintype "passive"))
    )
    (net (code "36") (name "/XTAL1") (class "Default")
      (node (ref "C16") (pin "2") (pinfunction "2_2") (pintype "passive"))
      (node (ref "U11") (pin "7") (pinfunction "PB6_(PCINT6/XTAL1/TOSC1)_7") (pintype "passive"))
      (node (ref "Y1") (pin "1") (pinfunction "OSC1_1") (pintype "passive"))
    )
    (net (code "37") (name "/XTAL2") (class "Default")
      (node (ref "C19") (pin "2") (pinfunction "2_2") (pintype "passive"))
      (node (ref "U11") (pin "8") (pinfunction "PB7_(PCINT7/XTAL2/TOSC2)_8") (pintype "passive"))
      (node (ref "Y1") (pin "2") (pinfunction "OSC2_2") (pintype "passive"))
    )
    (net (code "38") (name "/YOFF+") (class "Default")
      (node (ref "HMC1") (pin "15") (pinfunction "OFFSET+(B)_15") (pintype "passive"))
      (node (ref "R41") (pin "2") (pinfunction "2_2") (pintype "passive"))
    )
    (net (code "39") (name "/YOFF-") (class "Default")
      (node (ref "HMC1") (pin "10") (pinfunction "OFFSET-(B)_10") (pintype "passive"))
      (node (ref "R41") (pin "1") (pinfunction "1_1") (pintype "passive"))
    )
    (net (code "40") (name "/ZOFF+") (class "Default")
      (node (ref "R40") (pin "2") (pinfunction "2_2") (pintype "passive"))
      (node (ref "U15") (pin "2") (pinfunction "OFFSET+_2") (pintype "passive"))
    )
    (net (code "41") (name "/ZOFF-") (class "Default")
      (node (ref "R40") (pin "1") (pinfunction "1_1") (pintype "passive"))
      (node (ref "U15") (pin "6") (pinfunction "OFFSET-_6") (pintype "passive"))
    )
    (net (code "42") (name "3V3D") (class "Default")
      (node (ref "C9") (pin "1") (pinfunction "1_1") (pintype "passive"))
      (node (ref "D3") (pin "1") (pinfunction "K_1") (pintype "passive"))
      (node (ref "R48") (pin "1") (pinfunction "1_1") (pintype "passive"))
      (node (ref "U1") (pin "5") (pinfunction "OUT_5") (pintype "power_in"))
    )
    (net (code "43") (name "5V0A") (class "Default")
      (node (ref "C1") (pin "2") (pinfunction "2_2") (pintype "passive"))
      (node (ref "C10") (pin "2") (pinfunction "2_2") (pintype "passive"))
      (node (ref "C2") (pin "2") (pinfunction "2_2") (pintype "passive"))
      (node (ref "C3") (pin "2") (pinfunction "2_2") (pintype "passive"))
      (node (ref "C37") (pin "2") (pinfunction "2_2") (pintype "passive"))
      (node (ref "C38") (pin "2") (pinfunction "2_2") (pintype "passive"))
      (node (ref "C39") (pin "2") (pinfunction "2_2") (pintype "passive"))
      (node (ref "C6") (pin "2") (pinfunction "2_2") (pintype "passive"))
      (node (ref "D1") (pin "1") (pinfunction "A_1") (pintype "passive"))
      (node (ref "D2") (pin "2") (pinfunction "K_2") (pintype "passive"))
      (node (ref "F1") (pin "1") (pinfunction "1_1") (pintype "passive"))
      (node (ref "R1") (pin "2") (pinfunction "2_2") (pintype "passive"))
      (node (ref "R15") (pin "2") (pinfunction "2_2") (pintype "passive"))
      (node (ref "R2") (pin "2") (pinfunction "2_2") (pintype "passive"))
      (node (ref "R46") (pin "2") (pinfunction "2_2") (pintype "passive"))
      (node (ref "U16") (pin "7") (pinfunction "V+_7") (pintype "power_in"))
      (node (ref "U17") (pin "7") (pinfunction "V+_7") (pintype "power_in"))
      (node (ref "U18") (pin "7") (pinfunction "V+_7") (pintype "power_in"))
      (node (ref "U2") (pin "3") (pinfunction "OUT_3") (pintype "power_in"))
      (node (ref "U3") (pin "8") (pinfunction "V+_8") (pintype "power_in"))
      (node (ref "U6") (pin "8") (pinfunction "V+_8") (pintype "power_in"))
    )
    (net (code "44") (name "5V0ADS") (class "Default")
      (node (ref "C20") (pin "2") (pinfunction "2_2") (pintype "passive"))
      (node (ref "C22") (pin "2") (pinfunction "2_2") (pintype "passive"))
      (node (ref "C27") (pin "2") (pinfunction "2_2") (pintype "passive"))
      (node (ref "C29") (pin "2") (pinfunction "2_2") (pintype "passive"))
      (node (ref "C32") (pin "2") (pinfunction "2_2") (pintype "passive"))
      (node (ref "C34") (pin "2") (pinfunction "2_2") (pintype "passive"))
      (node (ref "C4") (pin "2") (pinfunction "2_2") (pintype "passive"))
      (node (ref "F1") (pin "2") (pinfunction "2_2") (pintype "passive"))
      (node (ref "R33") (pin "2") (pinfunction "2_2") (pintype "passive"))
      (node (ref "U10") (pin "8") (pinfunction "VDD_8") (pintype "passive"))
      (node (ref "U12") (pin "8") (pinfunction "VDD_8") (pintype "passive"))
      (node (ref "U14") (pin "8") (pinfunction "VDD_8") (pintype "passive"))
    )
    (net (code "45") (name "5V0D") (class "Default")
      (node (ref "C11") (pin "2") (pinfunction "2_2") (pintype "passive"))
      (node (ref "C12") (pin "2") (pinfunction "2_2") (pintype "passive"))
      (node (ref "C17") (pin "2") (pinfunction "2_2") (pintype "passive"))
      (node (ref "C18") (pin "2") (pinfunction "2_2") (pintype "passive"))
      (node (ref "C25") (pin "2") (pinfunction "2_2") (pintype "passive"))
      (node (ref "C43") (pin "2") (pinfunction "2_2") (pintype "passive"))
      (node (ref "D4") (pin "1") (pinfunction "A_1") (pintype "passive"))
      (node (ref "D5") (pin "2") (pinfunction "K_2") (pintype "passive"))
      (node (ref "H1") (pin "2") (pinfunction "2_2") (pintype "passive"))
      (node (ref "R20") (pin "1") (pinfunction "1_1") (pintype "passive"))
      (node (ref "R21") (pin "1") (pinfunction "1_1") (pintype "passive"))
      (node (ref "R22") (pin "1") (pinfunction "1_1") (pintype "passive"))
      (node (ref "R26") (pin "1") (pinfunction "1_1") (pintype "passive"))
      (node (ref "R27") (pin "1") (pinfunction "1_1") (pintype "passive"))
      (node (ref "R28") (pin "1") (pinfunction "1_1") (pintype "passive"))
      (node (ref "R29") (pin "1") (pinfunction "1_1") (pintype "passive"))
      (node (ref "R47") (pin "1") (pinfunction "1_1") (pintype "passive"))
      (node (ref "R6") (pin "1") (pinfunction "1_1") (pintype "passive"))
      (node (ref "U1") (pin "1") (pinfunction "IN_1") (pintype "power_in"))
      (node (ref "U11") (pin "18") (pinfunction "AVCC_18") (pintype "passive"))
      (node (ref "U11") (pin "4") (pinfunction "VCC_4") (pintype "passive"))
      (node (ref "U11") (pin "6") (pinfunction "VCC_6") (pintype "passive"))
      (node (ref "U13") (pin "14") (pinfunction "VCC_14") (pintype "power_in"))
      (node (ref "U7") (pin "3") (pinfunction "OUT_3") (pintype "power_in"))
    )
    (net (code "46") (name "GNDA") (class "Default")
      (node (ref "C1") (pin "1") (pinfunction "1_1") (pintype "passive"))
      (node (ref "C10") (pin "1") (pinfunction "1_1") (pintype "passive"))
      (node (ref "C2") (pin "1") (pinfunction "1_1") (pintype "passive"))
      (node (ref "C20") (pin "1") (pinfunction "1_1") (pintype "passive"))
      (node (ref "C22") (pin "1") (pinfunction "1_1") (pintype "passive"))
      (node (ref "C24") (pin "2") (pinfunction "2_2") (pintype "passive"))
      (node (ref "C27") (pin "1") (pinfunction "1_1") (pintype "passive"))
      (node (ref "C29") (pin "1") (pinfunction "1_1") (pintype "passive"))
      (node (ref "C3") (pin "1") (pinfunction "1_1") (pintype "passive"))
      (node (ref "C31") (pin "2") (pinfunction "2_2") (pintype "passive"))
      (node (ref "C32") (pin "1") (pinfunction "1_1") (pintype "passive"))
      (node (ref "C34") (pin "1") (pinfunction "1_1") (pintype "passive"))
      (node (ref "C36") (pin "2") (pinfunction "2_2") (pintype "passive"))
      (node (ref "C37") (pin "1") (pinfunction "1_1") (pintype "passive"))
      (node (ref "C38") (pin "1") (pinfunction "1_1") (pintype "passive"))
      (node (ref "C39") (pin "1") (pinfunction "1_1") (pintype "passive"))
      (node (ref "C4") (pin "1") (pinfunction "1_1") (pintype "passive"))
      (node (ref "C44") (pin "1") (pinfunction "1_1") (pintype "passive"))
      (node (ref "C45") (pin "1") (pinfunction "1_1") (pintype "passive"))
      (node (ref "C46") (pin "1") (pinfunction "1_1") (pintype "passive"))
      (node (ref "C5") (pin "1") (pinfunction "1_1") (pintype "passive"))
      (node (ref "C6") (pin "1") (pinfunction "1_1") (pintype "passive"))
      (node (ref "C7") (pin "1") (pinfunction "1_1") (pintype "passive"))
      (node (ref "D2") (pin "1") (pinfunction "A_1") (pintype "passive"))
      (node (ref "F2") (pin "1") (pinfunction "1_1") (pintype "passive"))
      (node (ref "HMC1") (pin "1") (pinfunction "GND1(A)_1") (pintype "passive"))
      (node (ref "HMC1") (pin "13") (pinfunction "GND2(B)_13") (pintype "passive"))
      (node (ref "HMC1") (pin "18") (pinfunction "GND_PLN_18") (pintype "passive"))
      (node (ref "HMC1") (pin "20") (pinfunction "S/R-(A)_20") (pintype "passive"))
      (node (ref "HMC1") (pin "6") (pinfunction "GND2(A)_6") (pintype "passive"))
      (node (ref "HMC1") (pin "7") (pinfunction "S/R-(B)_7") (pintype "passive"))
      (node (ref "HMC1") (pin "8") (pinfunction "GND1(B)_8") (pintype "passive"))
      (node (ref "J5") (pin "1") (pinfunction "1_1") (pintype "passive"))
      (node (ref "P1") (pin "5") (pinfunction "5_5") (pintype "passive"))
      (node (ref "R12") (pin "1") (pinfunction "1_1") (pintype "passive"))
      (node (ref "R13") (pin "1") (pinfunction "1_1") (pintype "passive"))
      (node (ref "R19") (pin "1") (pinfunction "1_1") (pintype "passive"))
      (node (ref "R23") (pin "1") (pinfunction "1_1") (pintype "passive"))
      (node (ref "R24") (pin "1") (pinfunction "1_1") (pintype "passive"))
      (node (ref "R34") (pin "1") (pinfunction "1_1") (pintype "passive"))
      (node (ref "R38") (pin "1") (pinfunction "1_1") (pintype "passive"))
      (node (ref "U10") (pin "3") (pinfunction "GND_3") (pintype "passive"))
      (node (ref "U10") (pin "6") (pinfunction "A2_6") (pintype "passive"))
      (node (ref "U10") (pin "7") (pinfunction "A3_7") (pintype "passive"))
      (node (ref "U12") (pin "3") (pinfunction "GND_3") (pintype "passive"))
      (node (ref "U12") (pin "6") (pinfunction "A2_6") (pintype "passive"))
      (node (ref "U12") (pin "7") (pinfunction "A3_7") (pintype "passive"))
      (node (ref "U14") (pin "3") (pinfunction "GND_3") (pintype "passive"))
      (node (ref "U14") (pin "6") (pinfunction "A2_6") (pintype "passive"))
      (node (ref "U14") (pin "7") (pinfunction "A3_7") (pintype "passive"))
      (node (ref "U15") (pin "3") (pinfunction "S/R-_3") (pintype "passive"))
      (node (ref "U15") (pin "4") (pinfunction "GND_4") (pintype "passive"))
      (node (ref "U16") (pin "4") (pinfunction "V-_4") (pintype "power_in"))
      (node (ref "U17") (pin "4") (pinfunction "V-_4") (pintype "power_in"))
      (node (ref "U18") (pin "4") (pinfunction "V-_4") (pintype "power_in"))
      (node (ref "U2") (pin "2") (pinfunction "GND_2") (pintype "power_in"))
      (node (ref "U3") (pin "4") (pinfunction "V-_4") (pintype "power_in"))
      (node (ref "U4") (pin "2") (pinfunction "-V_2") (pintype "passive"))
      (node (ref "U5") (pin "2") (pinfunction "-V_2") (pintype "passive"))
      (node (ref "U6") (pin "4") (pinfunction "V-_4") (pintype "power_in"))
      (node (ref "U8") (pin "2") (pinfunction "-V_2") (pintype "passive"))
    )
    (net (code "47") (name "GNDD") (class "Default")
      (node (ref "C11") (pin "1") (pinfunction "1_1") (pintype "passive"))
      (node (ref "C12") (pin "1") (pinfunction "1_1") (pintype "passive"))
      (node (ref "C13") (pin "1") (pinfunction "1_1") (pintype "passive"))
      (node (ref "C14") (pin "1") (pinfunction "1_1") (pintype "passive"))
      (node (ref "C15") (pin "1") (pinfunction "1_1") (pintype "passive"))
      (node (ref "C16") (pin "1") (pinfunction "1_1") (pintype "passive"))
      (node (ref "C17") (pin "1") (pinfunction "1_1") (pintype "passive"))
      (node (ref "C18") (pin "1") (pinfunction "1_1") (pintype "passive"))
      (node (ref "C19") (pin "1") (pinfunction "1_1") (pintype "passive"))
      (node (ref "C25") (pin "1") (pinfunction "1_1") (pintype "passive"))
      (node (ref "C26") (pin "1") (pinfunction "1_1") (pintype "passive"))
      (node (ref "C43") (pin "1") (pinfunction "1_1") (pintype "passive"))
      (node (ref "C8") (pin "1") (pinfunction "1_1") (pintype "passive"))
      (node (ref "C9") (pin "2") (pinfunction "2_2") (pintype "passive"))
      (node (ref "D3") (pin "2") (pinfunction "A_2") (pintype "passive"))
      (node (ref "D5") (pin "1") (pinfunction "A_1") (pintype "passive"))
      (node (ref "F2") (pin "2") (pinfunction "2_2") (pintype "passive"))
      (node (ref "H1") (pin "1") (pinfunction "1_1") (pintype "passive"))
      (node (ref "P1") (pin "3") (pinfunction "3_3") (pintype "passive"))
      (node (ref "R14") (pin "1") (pinfunction "1_1") (pintype "passive"))
      (node (ref "R30") (pin "5") (pinfunction "5_5") (pintype "passive"))
      (node (ref "R30") (pin "6") (pinfunction "6_6") (pintype "passive"))
      (node (ref "R30") (pin "7") (pinfunction "7_7") (pintype "passive"))
      (node (ref "R30") (pin "8") (pinfunction "8_8") (pintype "passive"))
      (node (ref "U1") (pin "2") (pinfunction "GND_2") (pintype "power_in"))
      (node (ref "U11") (pin "21") (pinfunction "GND_21") (pintype "passive"))
      (node (ref "U11") (pin "3") (pinfunction "GND_3") (pintype "passive"))
      (node (ref "U11") (pin "5") (pinfunction "GND_5") (pintype "passive"))
      (node (ref "U13") (pin "7") (pinfunction "GND_7") (pintype "passive"))
      (node (ref "U7") (pin "2") (pinfunction "GND_2") (pintype "power_in"))
      (node (ref "U9") (pin "5") (pinfunction "GND_5") (pintype "passive"))
    )
    (net (code "48") (name "Net-(P1-Pad1)") (class "Default")
      (node (ref "P1") (pin "1") (pinfunction "1_1") (pintype "passive"))
      (node (ref "R7") (pin "2") (pinfunction "2_2") (pintype "passive"))
    )
    (net (code "49") (name "Net-(P1-Pad2)") (class "Default")
      (node (ref "P1") (pin "2") (pinfunction "2_2") (pintype "passive"))
      (node (ref "R11") (pin "2") (pinfunction "2_2") (pintype "passive"))
    )
    (net (code "50") (name "Net-(R8-BOT)") (class "Default")
      (node (ref "R3") (pin "1") (pinfunction "1_1") (pintype "passive"))
      (node (ref "R8") (pin "3") (pinfunction "BOT_3") (pintype "passive"))
    )
    (net (code "51") (name "Net-(R8-TAP)") (class "Default")
      (node (ref "R8") (pin "2") (pinfunction "TAP_2") (pintype "passive"))
      (node (ref "U3") (pin "3") (pinfunction "IN+_3") (pintype "input"))
    )
    (net (code "52") (name "Net-(R8-TOP)") (class "Default")
      (node (ref "R12") (pin "2") (pinfunction "2_2") (pintype "passive"))
      (node (ref "R8") (pin "1") (pinfunction "TOP_1") (pintype "passive"))
    )
    (net (code "53") (name "Net-(R9-BOT)") (class "Default")
      (node (ref "R4") (pin "1") (pinfunction "1_1") (pintype "passive"))
      (node (ref "R9") (pin "3") (pinfunction "BOT_3") (pintype "passive"))
    )
    (net (code "54") (name "Net-(R9-TAP)") (class "Default")
      (node (ref "R9") (pin "2") (pinfunction "TAP_2") (pintype "passive"))
      (node (ref "U6") (pin "3") (pinfunction "IN+_3") (pintype "input"))
    )
    (net (code "55") (name "Net-(R9-TOP)") (class "Default")
      (node (ref "R13") (pin "2") (pinfunction "2_2") (pintype "passive"))
      (node (ref "R9") (pin "1") (pinfunction "TOP_1") (pintype "passive"))
    )
    (net (code "56") (name "Net-(R17-BOT)") (class "Default")
      (node (ref "R16") (pin "1") (pinfunction "1_1") (pintype "passive"))
      (node (ref "R17") (pin "3") (pinfunction "BOT_3") (pintype "passive"))
    )
    (net (code "57") (name "Net-(R17-TAP)") (class "Default")
      (node (ref "R17") (pin "2") (pinfunction "TAP_2") (pintype "passive"))
      (node (ref "U3") (pin "5") (pinfunction "IN+_5") (pintype "input"))
    )
    (net (code "58") (name "Net-(R17-TOP)") (class "Default")
      (node (ref "R17") (pin "1") (pinfunction "TOP_1") (pintype "passive"))
      (node (ref "R19") (pin "2") (pinfunction "2_2") (pintype "passive"))
    )
    (net (code "59") (name "Net-(R43-Pad2)") (class "Default")
      (node (ref "R43") (pin "2") (pinfunction "2_2") (pintype "passive"))
      (node (ref "U16") (pin "1") (pinfunction "OS_NUL_1") (pintype "passive"))
    )
    (net (code "60") (name "Net-(R44-Pad2)") (class "Default")
      (node (ref "R44") (pin "2") (pinfunction "2_2") (pintype "passive"))
      (node (ref "U17") (pin "1") (pinfunction "OS_NUL_1") (pintype "passive"))
    )
    (net (code "61") (name "Net-(R45-Pad2)") (class "Default")
      (node (ref "R45") (pin "2") (pinfunction "2_2") (pintype "passive"))
      (node (ref "U18") (pin "1") (pinfunction "OS_NUL_1") (pintype "passive"))
    )
    (net (code "62") (name "Net-(U1-BYP)") (class "Default")
      (node (ref "C8") (pin "2") (pinfunction "2_2") (pintype "passive"))
      (node (ref "U1") (pin "4") (pinfunction "BYP_4") (pintype "bidirectional"))
    )
    (net (code "63") (name "Net-(U4-+V)") (class "Default")
      (node (ref "R1") (pin "1") (pinfunction "1_1") (pintype "passive"))
      (node (ref "R3") (pin "2") (pinfunction "2_2") (pintype "passive"))
      (node (ref "U4") (pin "1") (pinfunction "+V_1") (pintype "passive"))
    )
    (net (code "64") (name "Net-(U5-+V)") (class "Default")
      (node (ref "R2") (pin "1") (pinfunction "1_1") (pintype "passive"))
      (node (ref "R4") (pin "2") (pinfunction "2_2") (pintype "passive"))
      (node (ref "U5") (pin "1") (pinfunction "+V_1") (pintype "passive"))
    )
    (net (code "65") (name "Net-(U8-+V)") (class "Default")
      (node (ref "R15") (pin "1") (pinfunction "1_1") (pintype "passive"))
      (node (ref "R16") (pin "2") (pinfunction "2_2") (pintype "passive"))
      (node (ref "U8") (pin "1") (pinfunction "+V_1") (pintype "passive"))
    )
    (net (code "66") (name "Net-(U10-A0)") (class "Default")
      (node (ref "C24") (pin "1") (pinfunction "1_1") (pintype "passive"))
      (node (ref "R25") (pin "2") (pinfunction "2_2") (pintype "passive"))
      (node (ref "U10") (pin "4") (pinfunction "A0_4") (pintype "passive"))
    )
    (net (code "67") (name "Net-(U10-ADDR)") (class "Default")
      (node (ref "R23") (pin "2") (pinfunction "2_2") (pintype "passive"))
      (node (ref "U10") (pin "1") (pinfunction "ADDR_1") (pintype "passive"))
    )
    (net (code "68") (name "Net-(U11-AREF)") (class "Default")
      (node (ref "C26") (pin "2") (pinfunction "2_2") (pintype "passive"))
      (node (ref "U11") (pin "20") (pinfunction "AREF_20") (pintype "passive"))
    )
    (net (code "69") (name "Net-(U11-PC0_(ADC0{slash}PCINT8))") (class "Default")
      (node (ref "R26") (pin "2") (pinfunction "2_2") (pintype "passive"))
      (node (ref "R30") (pin "1") (pinfunction "1_1") (pintype "passive"))
      (node (ref "U11") (pin "23") (pinfunction "PC0_(ADC0/PCINT8)_23") (pintype "passive"))
    )
    (net (code "70") (name "Net-(U11-PC1_(ADC1{slash}PCINT9))") (class "Default")
      (node (ref "R27") (pin "2") (pinfunction "2_2") (pintype "passive"))
      (node (ref "R30") (pin "2") (pinfunction "2_2") (pintype "passive"))
      (node (ref "U11") (pin "24") (pinfunction "PC1_(ADC1/PCINT9)_24") (pintype "passive"))
    )
    (net (code "71") (name "Net-(U11-PC2_(ADC2{slash}PCINT10))") (class "Default")
      (node (ref "R28") (pin "2") (pinfunction "2_2") (pintype "passive"))
      (node (ref "R30") (pin "3") (pinfunction "3_3") (pintype "passive"))
      (node (ref "U11") (pin "25") (pinfunction "PC2_(ADC2/PCINT10)_25") (pintype "passive"))
    )
    (net (code "72") (name "Net-(U11-PC3_(ADC3{slash}PCINT11))") (class "Default")
      (node (ref "R29") (pin "2") (pinfunction "2_2") (pintype "passive"))
      (node (ref "R30") (pin "4") (pinfunction "4_4") (pintype "passive"))
      (node (ref "U11") (pin "26") (pinfunction "PC3_(ADC3/PCINT11)_26") (pintype "passive"))
    )
    (net (code "73") (name "Net-(U12-A0)") (class "Default")
      (node (ref "C31") (pin "1") (pinfunction "1_1") (pintype "passive"))
      (node (ref "R35") (pin "2") (pinfunction "2_2") (pintype "passive"))
      (node (ref "U12") (pin "4") (pinfunction "A0_4") (pintype "passive"))
    )
    (net (code "74") (name "Net-(U12-ADDR)") (class "Default")
      (node (ref "R33") (pin "1") (pinfunction "1_1") (pintype "passive"))
      (node (ref "U12") (pin "1") (pinfunction "ADDR_1") (pintype "passive"))
    )
    (net (code "75") (name "Net-(U14-A0)") (class "Default")
      (node (ref "C36") (pin "1") (pinfunction "1_1") (pintype "passive"))
      (node (ref "R39") (pin "2") (pinfunction "2_2") (pintype "passive"))
      (node (ref "U14") (pin "4") (pinfunction "A0_4") (pintype "passive"))
    )
    (net (code "76") (name "Net-(U16-TAB)") (class "Default")
      (node (ref "C40") (pin "2") (pinfunction "2_2") (pintype "passive"))
      (node (ref "R43") (pin "1") (pinfunction "1_1") (pintype "passive"))
      (node (ref "U16") (pin "8") (pinfunction "TAB_8") (pintype "passive"))
    )
    (net (code "77") (name "Net-(U17-TAB)") (class "Default")
      (node (ref "C41") (pin "2") (pinfunction "2_2") (pintype "passive"))
      (node (ref "R44") (pin "1") (pinfunction "1_1") (pintype "passive"))
      (node (ref "U17") (pin "8") (pinfunction "TAB_8") (pintype "passive"))
    )
    (net (code "78") (name "Net-(U18-TAB)") (class "Default")
      (node (ref "C42") (pin "2") (pinfunction "2_2") (pintype "passive"))
      (node (ref "R45") (pin "1") (pinfunction "1_1") (pintype "passive"))
      (node (ref "U18") (pin "8") (pinfunction "TAB_8") (pintype "passive"))
    )
    (net (code "79") (name "RS485_VCC") (class "Default")
      (node (ref "C15") (pin "2") (pinfunction "2_2") (pintype "passive"))
      (node (ref "R47") (pin "2") (pinfunction "2_2") (pintype "passive"))
      (node (ref "R48") (pin "2") (pinfunction "2_2") (pintype "passive"))
      (node (ref "R5") (pin "2") (pinfunction "2_2") (pintype "passive"))
      (node (ref "U9") (pin "8") (pinfunction "VCC_8") (pintype "passive"))
    )
    (net (code "80") (name "VCC_IN") (class "Default")
      (node (ref "C13") (pin "2") (pinfunction "2_2") (pintype "passive"))
      (node (ref "C14") (pin "2") (pinfunction "2_2") (pintype "passive"))
      (node (ref "C5") (pin "2") (pinfunction "2_2") (pintype "passive"))
      (node (ref "C7") (pin "2") (pinfunction "2_2") (pintype "passive"))
      (node (ref "D1") (pin "2") (pinfunction "K_2") (pintype "passive"))
      (node (ref "D4") (pin "2") (pinfunction "K_2") (pintype "passive"))
      (node (ref "J3") (pin "1") (pinfunction "1_1") (pintype "passive"))
      (node (ref "P1") (pin "4") (pinfunction "4_4") (pintype "passive"))
      (node (ref "U2") (pin "1") (pinfunction "IN_1") (pintype "power_in"))
      (node (ref "U7") (pin "1") (pinfunction "IN_1") (pintype "power_in"))
    )
    (net (code "81") (name "Vbridge") (class "Default")
      (node (ref "C44") (pin "2") (pinfunction "2_2") (pintype "passive"))
      (node (ref "C45") (pin "2") (pinfunction "2_2") (pintype "passive"))
      (node (ref "C46") (pin "2") (pinfunction "2_2") (pintype "passive"))
      (node (ref "HMC1") (pin "11") (pinfunction "Vbridge(B)_11") (pintype "passive"))
      (node (ref "HMC1") (pin "4") (pinfunction "VBridge(A)_4") (pintype "passive"))
      (node (ref "R46") (pin "1") (pinfunction "1_1") (pintype "passive"))
      (node (ref "U15") (pin "7") (pinfunction "Vbridge_7") (pintype "passive"))
    )
    (net (code "82") (name "unconnected-(HMC1-NC-Pad19)") (class "Default")
      (node (ref "HMC1") (pin "19") (pinfunction "NC_19") (pintype "passive+no_connect"))
    )
    (net (code "83") (name "unconnected-(U4-NC-Pad3)") (class "Default")
      (node (ref "U4") (pin "3") (pinfunction "NC_3") (pintype "passive+no_connect"))
    )
    (net (code "84") (name "unconnected-(U5-NC-Pad3)") (class "Default")
      (node (ref "U5") (pin "3") (pinfunction "NC_3") (pintype "passive+no_connect"))
    )
    (net (code "85") (name "unconnected-(U6B-IN+-Pad5)") (class "Default")
      (node (ref "U6") (pin "5") (pinfunction "IN+_5") (pintype "input+no_connect"))
    )
    (net (code "86") (name "unconnected-(U6B-IN--Pad6)") (class "Default")
      (node (ref "U6") (pin "6") (pinfunction "IN-_6") (pintype "input+no_connect"))
    )
    (net (code "87") (name "unconnected-(U6B-OUT-Pad7)") (class "Default")
      (node (ref "U6") (pin "7") (pinfunction "OUT_7") (pintype "output+no_connect"))
    )
    (net (code "88") (name "unconnected-(U8-NC-Pad3)") (class "Default")
      (node (ref "U8") (pin "3") (pinfunction "NC_3") (pintype "passive+no_connect"))
    )
    (net (code "89") (name "unconnected-(U11-ADC6-Pad19)") (class "Default")
      (node (ref "U11") (pin "19") (pinfunction "ADC6_19") (pintype "passive+no_connect"))
    )
    (net (code "90") (name "unconnected-(U11-ADC7-Pad22)") (class "Default")
      (node (ref "U11") (pin "22") (pinfunction "ADC7_22") (pintype "passive+no_connect"))
    )
    (net (code "91") (name "unconnected-(U11-PB2_(PCINT2{slash}~{SS}{slash}OC1B)-Pad14)") (class "Default")
      (node (ref "U11") (pin "14") (pinfunction "PB2_(PCINT2/~{SS}/OC1B)_14") (pintype "passive+no_connect"))
    )
    (net (code "92") (name "unconnected-(U13-2A-Pad4)") (class "Default")
      (node (ref "U13") (pin "4") (pinfunction "2A_4") (pintype "input+no_connect"))
    )
    (net (code "93") (name "unconnected-(U13-2B-Pad5)") (class "Default")
      (node (ref "U13") (pin "5") (pinfunction "2B_5") (pintype "input+no_connect"))
    )
    (net (code "94") (name "unconnected-(U13-2Y-Pad6)") (class "Default")
      (node (ref "U13") (pin "6") (pinfunction "2Y_6") (pintype "output+no_connect"))
    )
    (net (code "95") (name "unconnected-(U13-3A-Pad9)") (class "Default")
      (node (ref "U13") (pin "9") (pinfunction "3A_9") (pintype "input+no_connect"))
    )
    (net (code "96") (name "unconnected-(U13-3B-Pad10)") (class "Default")
      (node (ref "U13") (pin "10") (pinfunction "3B_10") (pintype "input+no_connect"))
    )
    (net (code "97") (name "unconnected-(U13-3Y-Pad8)") (class "Default")
      (node (ref "U13") (pin "8") (pinfunction "3Y_8") (pintype "output+no_connect"))
    )
    (net (code "98") (name "unconnected-(U13-4A-Pad12)") (class "Default")
      (node (ref "U13") (pin "12") (pinfunction "4A_12") (pintype "input+no_connect"))
    )
    (net (code "99") (name "unconnected-(U13-4B-Pad13)") (class "Default")
      (node (ref "U13") (pin "13") (pinfunction "4B_13") (pintype "input+no_connect"))
    )
    (net (code "100") (name "unconnected-(U13-4Y-Pad11)") (class "Default")
      (node (ref "U13") (pin "11") (pinfunction "4Y_11") (pintype "output+no_connect"))
    )
  )
)
